# board_sch.net
KiCad netlist of a schematic drawn in Altium Designer
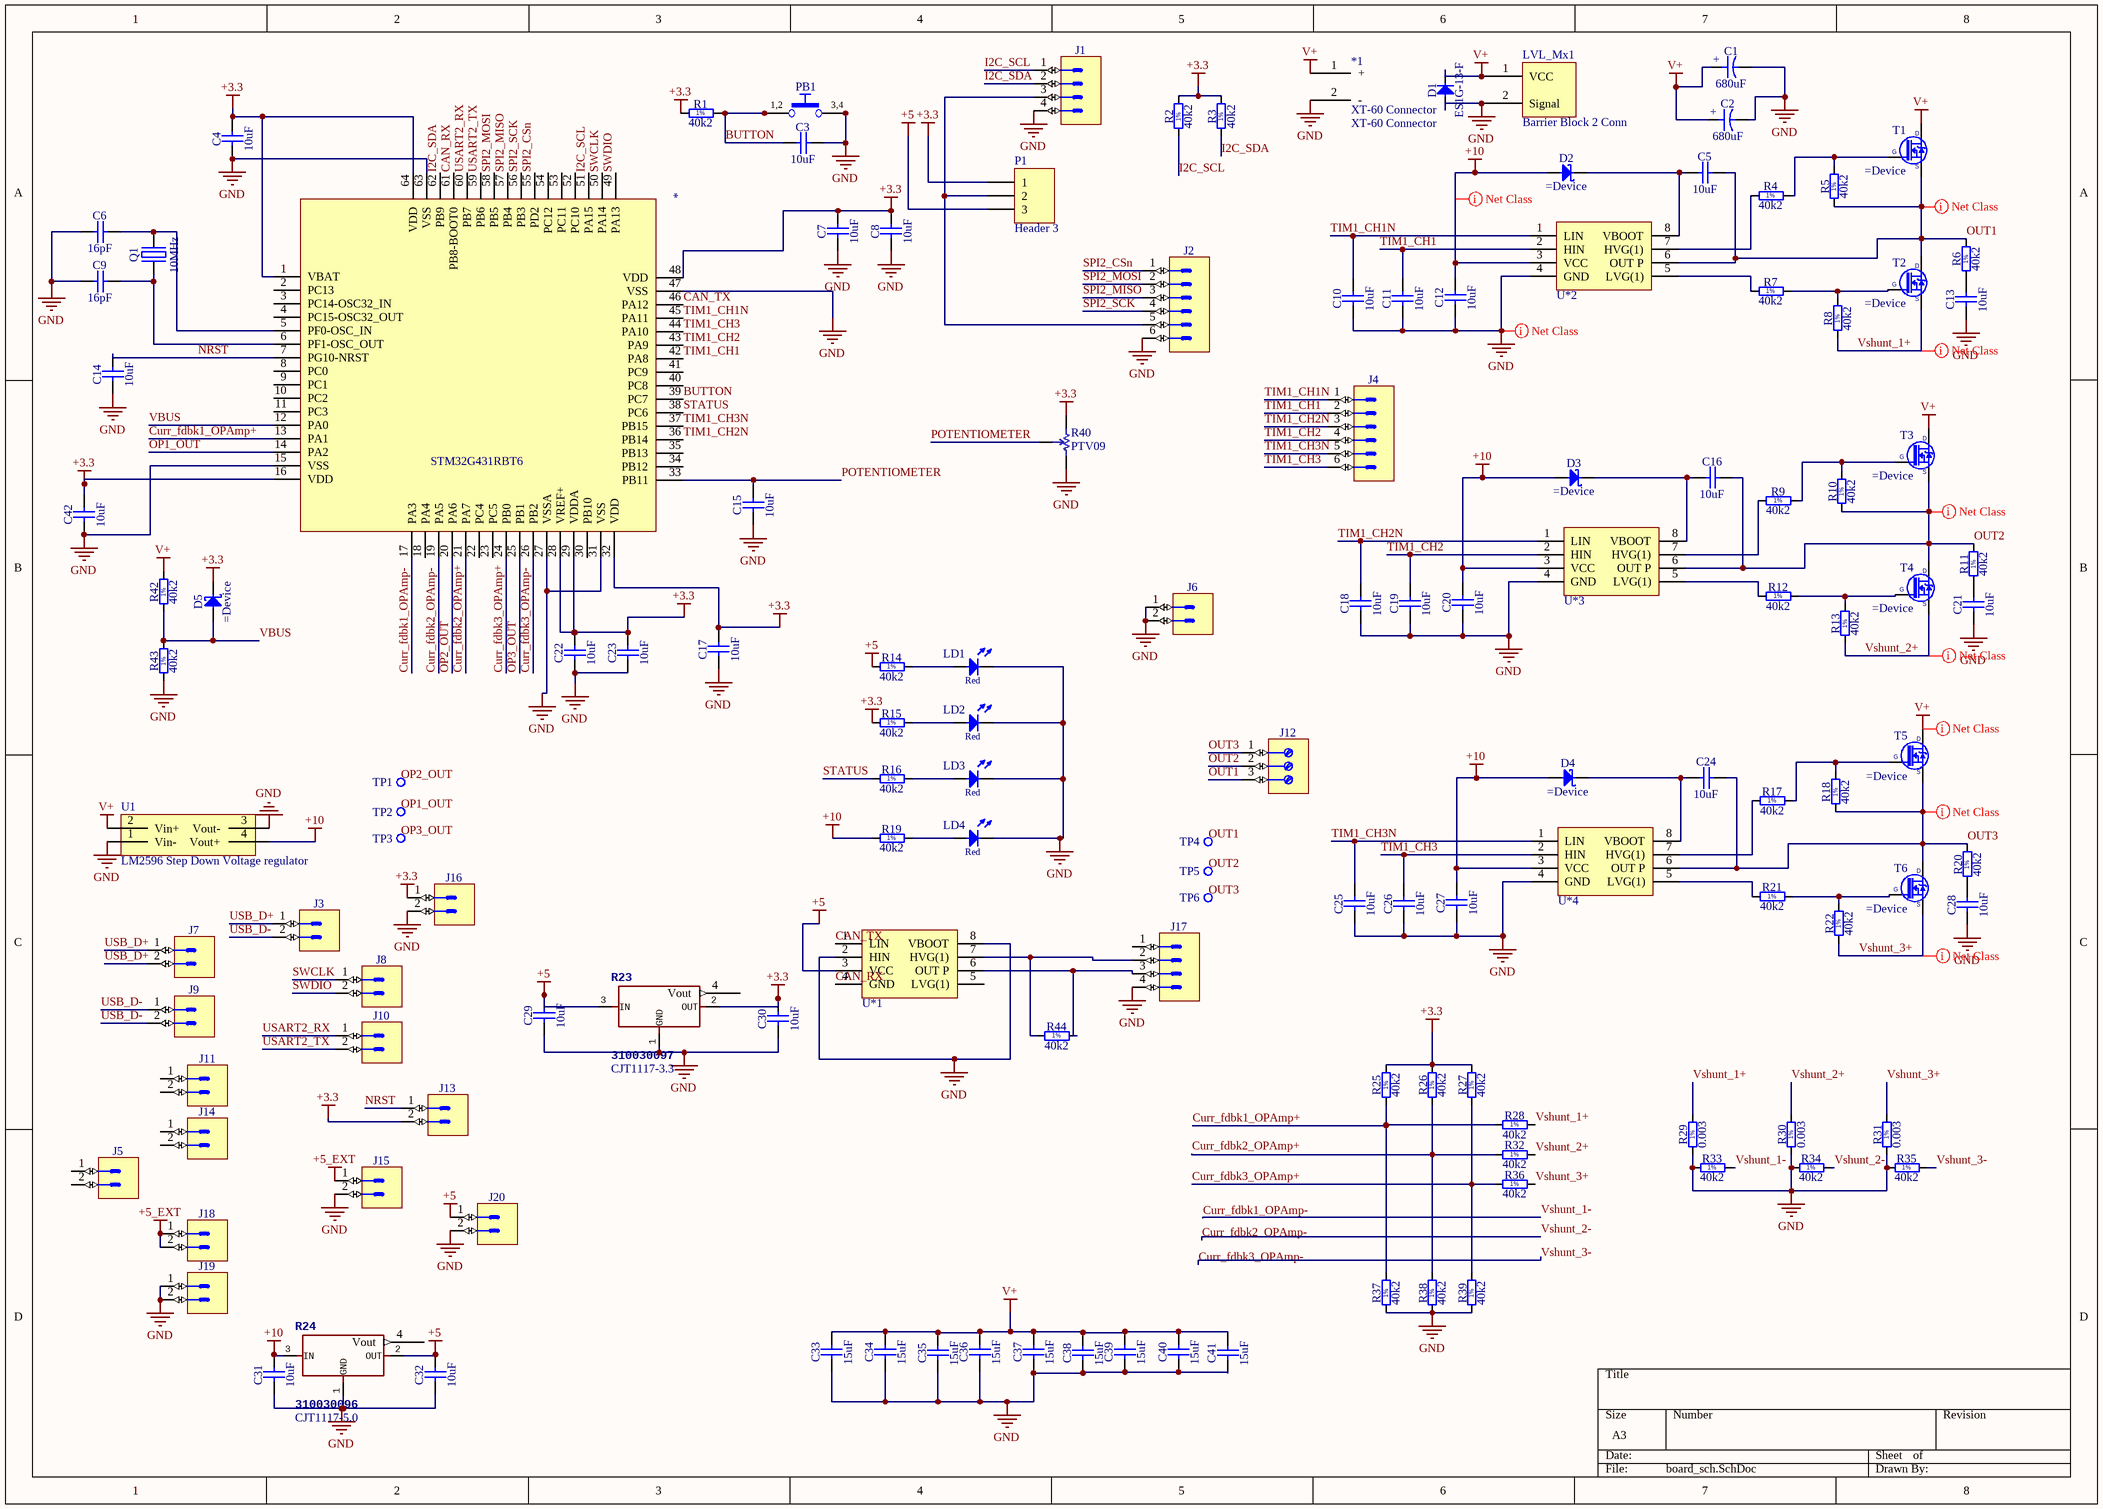
[diagram p0: board_sch.SchDoc]

(export (version "E")
  (design (tool "Eeschema 10.0.6"))
  (components
    (comp (ref "*")
      (value "STM32G431RBT6")
      (footprint "STM-LQFP64_L")
      (libsource (lib "lib") (part "STM32G431RBT6"))
    )
    (comp (ref "*1")
      (value "XT-60 Connector")
      (footprint "XT-60")
      (fields
        (field (name "MANUFACTURER") "POLOLU")
        (field (name "MANUFACTURER PART NUMBER") "XT60 YELLOW")
        (field (name "SUPPLIER PART NUMBER 1") "XT-60 Connector")
      )
      (libsource (lib "AltiumLibraryDDT") (part "XT-60 Connector"))
    )
    (comp (ref "C1")
      (value "680uF")
      (footprint "CAPAE1030X1020N")
      (description "Polarised capacitor")
      (fields
        (field (name "PART NUMBER") "CAE1030-1020_680UF_4V_20%")
        (field (name "VOLTAGE") "4V")
        (field (name "AUTHOR") "CERN DEM MR")
      )
      (libsource (lib "Capacitors") (part "Capacitor - polarized"))
    )
    (comp (ref "C2")
      (value "680uF")
      (footprint "CAPAE1030X1020N")
      (description "Polarised capacitor")
      (fields
        (field (name "PART NUMBER") "CAE1030-1020_680UF_4V_20%")
        (field (name "VOLTAGE") "4V")
        (field (name "AUTHOR") "CERN DEM MR")
      )
      (libsource (lib "Capacitors") (part "Capacitor - polarized"))
    )
    (comp (ref "C3")
      (value "10uF")
      (footprint "CAPC2012X135N")
      (description "Non-polarised capacitor")
      (fields
        (field (name "PART NUMBER") "CC0805_10UF_10V_10%_X7R")
        (field (name "VOLTAGE") "10V")
        (field (name "AUTHOR") "CERN DEM JLC")
      )
      (libsource (lib "Capacitors") (part "Capacitor - non polarized"))
    )
    (comp (ref "C4")
      (value "10uF")
      (footprint "CAPC2012X135N")
      (description "Non-polarised capacitor")
      (fields
        (field (name "PART NUMBER") "CC0805_10UF_10V_10%_X7R")
        (field (name "VOLTAGE") "10V")
        (field (name "AUTHOR") "CERN DEM JLC")
      )
      (libsource (lib "Capacitors") (part "Capacitor - non polarized"))
    )
    (comp (ref "C5")
      (value "10uF")
      (footprint "CAPC2012X135N")
      (description "Non-polarised capacitor")
      (fields
        (field (name "PART NUMBER") "CC0805_10UF_10V_10%_X7R")
        (field (name "VOLTAGE") "10V")
        (field (name "AUTHOR") "CERN DEM JLC")
      )
      (libsource (lib "Capacitors") (part "Capacitor - non polarized"))
    )
    (comp (ref "C6")
      (value "16pF")
      (footprint "CAPC2012X135N")
      (description "Non-polarised capacitor")
      (fields
        (field (name "PART NUMBER") "CC0805_10UF_10V_10%_X7R")
        (field (name "VOLTAGE") "10V")
        (field (name "AUTHOR") "CERN DEM JLC")
      )
      (libsource (lib "Capacitors") (part "Capacitor - non polarized"))
    )
    (comp (ref "C7")
      (value "10uF")
      (footprint "CAPC2012X135N")
      (description "Non-polarised capacitor")
      (fields
        (field (name "PART NUMBER") "CC0805_10UF_10V_10%_X7R")
        (field (name "VOLTAGE") "10V")
        (field (name "AUTHOR") "CERN DEM JLC")
      )
      (libsource (lib "Capacitors") (part "Capacitor - non polarized"))
    )
    (comp (ref "C8")
      (value "10uF")
      (footprint "CAPC2012X135N")
      (description "Non-polarised capacitor")
      (fields
        (field (name "PART NUMBER") "CC0805_10UF_10V_10%_X7R")
        (field (name "VOLTAGE") "10V")
        (field (name "AUTHOR") "CERN DEM JLC")
      )
      (libsource (lib "Capacitors") (part "Capacitor - non polarized"))
    )
    (comp (ref "C9")
      (value "16pF")
      (footprint "CAPC2012X135N")
      (description "Non-polarised capacitor")
      (fields
        (field (name "PART NUMBER") "CC0805_10UF_10V_10%_X7R")
        (field (name "VOLTAGE") "10V")
        (field (name "AUTHOR") "CERN DEM JLC")
      )
      (libsource (lib "Capacitors") (part "Capacitor - non polarized"))
    )
    (comp (ref "C10")
      (value "10uF")
      (footprint "CAPC2012X135N")
      (description "Non-polarised capacitor")
      (fields
        (field (name "PART NUMBER") "CC0805_10UF_10V_10%_X7R")
        (field (name "VOLTAGE") "10V")
        (field (name "AUTHOR") "CERN DEM JLC")
      )
      (libsource (lib "Capacitors") (part "Capacitor - non polarized"))
    )
    (comp (ref "C11")
      (value "10uF")
      (footprint "CAPC2012X135N")
      (description "Non-polarised capacitor")
      (fields
        (field (name "PART NUMBER") "CC0805_10UF_10V_10%_X7R")
        (field (name "VOLTAGE") "10V")
        (field (name "AUTHOR") "CERN DEM JLC")
      )
      (libsource (lib "Capacitors") (part "Capacitor - non polarized"))
    )
    (comp (ref "C12")
      (value "10uF")
      (footprint "CAPC2012X135N")
      (description "Non-polarised capacitor")
      (fields
        (field (name "PART NUMBER") "CC0805_10UF_10V_10%_X7R")
        (field (name "VOLTAGE") "10V")
        (field (name "AUTHOR") "CERN DEM JLC")
      )
      (libsource (lib "Capacitors") (part "Capacitor - non polarized"))
    )
    (comp (ref "C13")
      (value "10uF")
      (footprint "CAPC2012X135N")
      (description "Non-polarised capacitor")
      (fields
        (field (name "PART NUMBER") "CC0805_10UF_10V_10%_X7R")
        (field (name "VOLTAGE") "10V")
        (field (name "AUTHOR") "CERN DEM JLC")
      )
      (libsource (lib "Capacitors") (part "Capacitor - non polarized"))
    )
    (comp (ref "C14")
      (value "10uF")
      (footprint "CAPC2012X135N")
      (description "Non-polarised capacitor")
      (fields
        (field (name "PART NUMBER") "CC0805_10UF_10V_10%_X7R")
        (field (name "VOLTAGE") "10V")
        (field (name "AUTHOR") "CERN DEM JLC")
      )
      (libsource (lib "Capacitors") (part "Capacitor - non polarized"))
    )
    (comp (ref "C15")
      (value "10uF")
      (footprint "CAPC2012X135N")
      (description "Non-polarised capacitor")
      (fields
        (field (name "PART NUMBER") "CC0805_10UF_10V_10%_X7R")
        (field (name "VOLTAGE") "10V")
        (field (name "AUTHOR") "CERN DEM JLC")
      )
      (libsource (lib "Capacitors") (part "Capacitor - non polarized"))
    )
    (comp (ref "C16")
      (value "10uF")
      (footprint "CAPC2012X135N")
      (description "Non-polarised capacitor")
      (fields
        (field (name "PART NUMBER") "CC0805_10UF_10V_10%_X7R")
        (field (name "VOLTAGE") "10V")
        (field (name "AUTHOR") "CERN DEM JLC")
      )
      (libsource (lib "Capacitors") (part "Capacitor - non polarized"))
    )
    (comp (ref "C17")
      (value "10uF")
      (footprint "CAPC2012X135N")
      (description "Non-polarised capacitor")
      (fields
        (field (name "PART NUMBER") "CC0805_10UF_10V_10%_X7R")
        (field (name "VOLTAGE") "10V")
        (field (name "AUTHOR") "CERN DEM JLC")
      )
      (libsource (lib "Capacitors") (part "Capacitor - non polarized"))
    )
    (comp (ref "C18")
      (value "10uF")
      (footprint "CAPC2012X135N")
      (description "Non-polarised capacitor")
      (fields
        (field (name "PART NUMBER") "CC0805_10UF_10V_10%_X7R")
        (field (name "VOLTAGE") "10V")
        (field (name "AUTHOR") "CERN DEM JLC")
      )
      (libsource (lib "Capacitors") (part "Capacitor - non polarized"))
    )
    (comp (ref "C19")
      (value "10uF")
      (footprint "CAPC2012X135N")
      (description "Non-polarised capacitor")
      (fields
        (field (name "PART NUMBER") "CC0805_10UF_10V_10%_X7R")
        (field (name "VOLTAGE") "10V")
        (field (name "AUTHOR") "CERN DEM JLC")
      )
      (libsource (lib "Capacitors") (part "Capacitor - non polarized"))
    )
    (comp (ref "C20")
      (value "10uF")
      (footprint "CAPC2012X135N")
      (description "Non-polarised capacitor")
      (fields
        (field (name "PART NUMBER") "CC0805_10UF_10V_10%_X7R")
        (field (name "VOLTAGE") "10V")
        (field (name "AUTHOR") "CERN DEM JLC")
      )
      (libsource (lib "Capacitors") (part "Capacitor - non polarized"))
    )
    (comp (ref "C21")
      (value "10uF")
      (footprint "CAPC2012X135N")
      (description "Non-polarised capacitor")
      (fields
        (field (name "PART NUMBER") "CC0805_10UF_10V_10%_X7R")
        (field (name "VOLTAGE") "10V")
        (field (name "AUTHOR") "CERN DEM JLC")
      )
      (libsource (lib "Capacitors") (part "Capacitor - non polarized"))
    )
    (comp (ref "C22")
      (value "10uF")
      (footprint "CAPC2012X135N")
      (description "Non-polarised capacitor")
      (fields
        (field (name "PART NUMBER") "CC0805_10UF_10V_10%_X7R")
        (field (name "VOLTAGE") "10V")
        (field (name "AUTHOR") "CERN DEM JLC")
      )
      (libsource (lib "Capacitors") (part "Capacitor - non polarized"))
    )
    (comp (ref "C23")
      (value "10uF")
      (footprint "CAPC2012X135N")
      (description "Non-polarised capacitor")
      (fields
        (field (name "PART NUMBER") "CC0805_10UF_10V_10%_X7R")
        (field (name "VOLTAGE") "10V")
        (field (name "AUTHOR") "CERN DEM JLC")
      )
      (libsource (lib "Capacitors") (part "Capacitor - non polarized"))
    )
    (comp (ref "C24")
      (value "10uF")
      (footprint "CAPC2012X135N")
      (description "Non-polarised capacitor")
      (fields
        (field (name "PART NUMBER") "CC0805_10UF_10V_10%_X7R")
        (field (name "VOLTAGE") "10V")
        (field (name "AUTHOR") "CERN DEM JLC")
      )
      (libsource (lib "Capacitors") (part "Capacitor - non polarized"))
    )
    (comp (ref "C25")
      (value "10uF")
      (footprint "CAPC2012X135N")
      (description "Non-polarised capacitor")
      (fields
        (field (name "PART NUMBER") "CC0805_10UF_10V_10%_X7R")
        (field (name "VOLTAGE") "10V")
        (field (name "AUTHOR") "CERN DEM JLC")
      )
      (libsource (lib "Capacitors") (part "Capacitor - non polarized"))
    )
    (comp (ref "C26")
      (value "10uF")
      (footprint "CAPC2012X135N")
      (description "Non-polarised capacitor")
      (fields
        (field (name "PART NUMBER") "CC0805_10UF_10V_10%_X7R")
        (field (name "VOLTAGE") "10V")
        (field (name "AUTHOR") "CERN DEM JLC")
      )
      (libsource (lib "Capacitors") (part "Capacitor - non polarized"))
    )
    (comp (ref "C27")
      (value "10uF")
      (footprint "CAPC2012X135N")
      (description "Non-polarised capacitor")
      (fields
        (field (name "PART NUMBER") "CC0805_10UF_10V_10%_X7R")
        (field (name "VOLTAGE") "10V")
        (field (name "AUTHOR") "CERN DEM JLC")
      )
      (libsource (lib "Capacitors") (part "Capacitor - non polarized"))
    )
    (comp (ref "C28")
      (value "10uF")
      (footprint "CAPC2012X135N")
      (description "Non-polarised capacitor")
      (fields
        (field (name "PART NUMBER") "CC0805_10UF_10V_10%_X7R")
        (field (name "VOLTAGE") "10V")
        (field (name "AUTHOR") "CERN DEM JLC")
      )
      (libsource (lib "Capacitors") (part "Capacitor - non polarized"))
    )
    (comp (ref "C29")
      (value "10uF")
      (footprint "CAPC2012X135N")
      (description "Non-polarised capacitor")
      (fields
        (field (name "PART NUMBER") "CC0805_10UF_10V_10%_X7R")
        (field (name "VOLTAGE") "10V")
        (field (name "AUTHOR") "CERN DEM JLC")
      )
      (libsource (lib "Capacitors") (part "Capacitor - non polarized"))
    )
    (comp (ref "C30")
      (value "10uF")
      (footprint "CAPC2012X135N")
      (description "Non-polarised capacitor")
      (fields
        (field (name "PART NUMBER") "CC0805_10UF_10V_10%_X7R")
        (field (name "VOLTAGE") "10V")
        (field (name "AUTHOR") "CERN DEM JLC")
      )
      (libsource (lib "Capacitors") (part "Capacitor - non polarized"))
    )
    (comp (ref "C31")
      (value "10uF")
      (footprint "CAPC2012X135N")
      (description "Non-polarised capacitor")
      (fields
        (field (name "PART NUMBER") "CC0805_10UF_10V_10%_X7R")
        (field (name "VOLTAGE") "10V")
        (field (name "AUTHOR") "CERN DEM JLC")
      )
      (libsource (lib "Capacitors") (part "Capacitor - non polarized"))
    )
    (comp (ref "C32")
      (value "10uF")
      (footprint "CAPC2012X135N")
      (description "Non-polarised capacitor")
      (fields
        (field (name "PART NUMBER") "CC0805_10UF_10V_10%_X7R")
        (field (name "VOLTAGE") "10V")
        (field (name "AUTHOR") "CERN DEM JLC")
      )
      (libsource (lib "Capacitors") (part "Capacitor - non polarized"))
    )
    (comp (ref "C33")
      (value "15uF")
      (footprint "CAPC2012X135N")
      (description "Non-polarised capacitor")
      (fields
        (field (name "PART NUMBER") "CC0805_1.2PF_50V_0.25PF_NP0")
        (field (name "VOLTAGE") "50V")
        (field (name "AUTHOR") "CERN DEM JLC")
      )
      (libsource (lib "Capacitors") (part "Capacitor - non polarized"))
    )
    (comp (ref "C34")
      (value "15uF")
      (footprint "CAPC2012X135N")
      (description "Non-polarised capacitor")
      (fields
        (field (name "PART NUMBER") "CC0805_1.2PF_50V_0.25PF_NP0")
        (field (name "VOLTAGE") "50V")
        (field (name "AUTHOR") "CERN DEM JLC")
      )
      (libsource (lib "Capacitors") (part "Capacitor - non polarized"))
    )
    (comp (ref "C35")
      (value "15uF")
      (footprint "CAPC2012X135N")
      (description "Non-polarised capacitor")
      (fields
        (field (name "PART NUMBER") "CC0805_1.2PF_50V_0.25PF_NP0")
        (field (name "VOLTAGE") "50V")
        (field (name "AUTHOR") "CERN DEM JLC")
      )
      (libsource (lib "Capacitors") (part "Capacitor - non polarized"))
    )
    (comp (ref "C36")
      (value "15uF")
      (footprint "CAPC2012X135N")
      (description "Non-polarised capacitor")
      (fields
        (field (name "PART NUMBER") "CC0805_1.2PF_50V_0.25PF_NP0")
        (field (name "VOLTAGE") "50V")
        (field (name "AUTHOR") "CERN DEM JLC")
      )
      (libsource (lib "Capacitors") (part "Capacitor - non polarized"))
    )
    (comp (ref "C37")
      (value "15uF")
      (footprint "CAPC2012X135N")
      (description "Non-polarised capacitor")
      (fields
        (field (name "PART NUMBER") "CC0805_1.2PF_50V_0.25PF_NP0")
        (field (name "VOLTAGE") "50V")
        (field (name "AUTHOR") "CERN DEM JLC")
      )
      (libsource (lib "Capacitors") (part "Capacitor - non polarized"))
    )
    (comp (ref "C38")
      (value "15uF")
      (footprint "CAPC2012X135N")
      (description "Non-polarised capacitor")
      (fields
        (field (name "PART NUMBER") "CC0805_1.2PF_50V_0.25PF_NP0")
        (field (name "VOLTAGE") "50V")
        (field (name "AUTHOR") "CERN DEM JLC")
      )
      (libsource (lib "Capacitors") (part "Capacitor - non polarized"))
    )
    (comp (ref "C39")
      (value "15uF")
      (footprint "CAPC2012X135N")
      (description "Non-polarised capacitor")
      (fields
        (field (name "PART NUMBER") "CC0805_1.2PF_50V_0.25PF_NP0")
        (field (name "VOLTAGE") "50V")
        (field (name "AUTHOR") "CERN DEM JLC")
      )
      (libsource (lib "Capacitors") (part "Capacitor - non polarized"))
    )
    (comp (ref "C40")
      (value "15uF")
      (footprint "CAPC2012X135N")
      (description "Non-polarised capacitor")
      (fields
        (field (name "PART NUMBER") "CC0805_1.2PF_50V_0.25PF_NP0")
        (field (name "VOLTAGE") "50V")
        (field (name "AUTHOR") "CERN DEM JLC")
      )
      (libsource (lib "Capacitors") (part "Capacitor - non polarized"))
    )
    (comp (ref "C41")
      (value "15uF")
      (footprint "CAPC2012X135N")
      (description "Non-polarised capacitor")
      (fields
        (field (name "PART NUMBER") "CC0805_1.2PF_50V_0.25PF_NP0")
        (field (name "VOLTAGE") "50V")
        (field (name "AUTHOR") "CERN DEM JLC")
      )
      (libsource (lib "Capacitors") (part "Capacitor - non polarized"))
    )
    (comp (ref "C42")
      (value "10uF")
      (footprint "CAPC2012X135N")
      (description "Non-polarised capacitor")
      (fields
        (field (name "PART NUMBER") "CC0805_10UF_10V_10%_X7R")
        (field (name "VOLTAGE") "10V")
        (field (name "AUTHOR") "CERN DEM JLC")
      )
      (libsource (lib "Capacitors") (part "Capacitor - non polarized"))
    )
    (comp (ref "D1")
      (value "ES1G-13-F")
      (footprint "DIOM5226X230N")
      (description "Diode")
      (fields
        (field (name "VOLTAGE") "400V")
        (field (name "POWER") "1A")
        (field (name "AUTHOR") "CERN DEM JLC")
      )
      (libsource (lib "ICs And Semiconductors") (part "Diode"))
    )
    (comp (ref "D2")
      (value "~")
      (footprint "SOD3716X135N")
      (description "Schottky Diode")
      (libsource (lib "Diodes") (part "Diode Schottky"))
    )
    (comp (ref "D3")
      (value "~")
      (footprint "SOD3716X135N")
      (description "Schottky Diode")
      (libsource (lib "Diodes") (part "Diode Schottky"))
    )
    (comp (ref "D4")
      (value "~")
      (footprint "SOD3716X135N")
      (description "Schottky Diode")
      (libsource (lib "Diodes") (part "Diode Schottky"))
    )
    (comp (ref "D5")
      (value "~")
      (footprint "SOD3716X135N")
      (description "Schottky Diode")
      (libsource (lib "Diodes") (part "Diode Schottky"))
    )
    (comp (ref "J1")
      (value "KK®")
      (footprint "MOLEX_22-04-1041")
      (description "Connector 4 Male")
      (fields
        (field (name "PART NUMBER") "MOLEX_22-04-1041")
        (field (name "MANUFACTURER") "MOLEX")
        (field (name "AUTHOR") "CERN DEM JLC")
      )
      (libsource (lib "Connectors") (part "Connector 4 Male"))
    )
    (comp (ref "J2")
      (value "KK®")
      (footprint "MOLEX_22-27-2061")
      (description "Connector 6 Male")
      (fields
        (field (name "PART NUMBER") "MOLEX_22-27-2061")
        (field (name "MANUFACTURER") "MOLEX")
        (field (name "AUTHOR") "CERN DEM JMW")
      )
      (libsource (lib "Connectors") (part "Connector 6 Male"))
    )
    (comp (ref "J3")
      (value "Header 2")
      (footprint "SAMTEC_TSW-101-23-L-D")
      (description "Connector 2 Male")
      (fields
        (field (name "PART NUMBER") "SAMTEC_TSW-101-23-L-D")
        (field (name "MANUFACTURER") "SAMTEC")
        (field (name "AUTHOR") "CERN DEM MR")
      )
      (libsource (lib "Connectors") (part "Connector 2 Male"))
    )
    (comp (ref "J4")
      (value "~")
      (footprint "HARWIN_M22-F2010605")
      (description "Connector 6 Male")
      (fields
        (field (name "PART NUMBER") "HARWIN_M22-F2010605")
        (field (name "MANUFACTURER") "HARWIN")
        (field (name "AUTHOR") "CERN DEM JLC")
      )
      (libsource (lib "Connectors") (part "Connector 6 Male"))
    )
    (comp (ref "J5")
      (value "Header 2")
      (footprint "SAMTEC_TSW-101-23-L-D")
      (description "Connector 2 Male")
      (fields
        (field (name "PART NUMBER") "SAMTEC_TSW-101-23-L-D")
        (field (name "MANUFACTURER") "SAMTEC")
        (field (name "AUTHOR") "CERN DEM MR")
      )
      (libsource (lib "Connectors") (part "Connector 2 Male"))
    )
    (comp (ref "J6")
      (value "Header 2")
      (footprint "HARWIN_M22-2010205")
      (description "Connector 2 Male")
      (fields
        (field (name "PART NUMBER") "HARWIN_M22-2010205")
        (field (name "MANUFACTURER") "HARWIN")
        (field (name "AUTHOR") "CERN DEM JLC")
      )
      (libsource (lib "Connectors") (part "Connector 2 Male"))
    )
    (comp (ref "J7")
      (value "Header 2")
      (footprint "SAMTEC_TSW-101-23-L-D")
      (description "Connector 2 Male")
      (fields
        (field (name "PART NUMBER") "SAMTEC_TSW-101-23-L-D")
        (field (name "MANUFACTURER") "SAMTEC")
        (field (name "AUTHOR") "CERN DEM MR")
      )
      (libsource (lib "Connectors") (part "Connector 2 Male"))
    )
    (comp (ref "J8")
      (value "Header 2")
      (footprint "SAMTEC_TSW-101-23-L-D")
      (description "Connector 2 Male")
      (fields
        (field (name "PART NUMBER") "SAMTEC_TSW-101-23-L-D")
        (field (name "MANUFACTURER") "SAMTEC")
        (field (name "AUTHOR") "CERN DEM MR")
      )
      (libsource (lib "Connectors") (part "Connector 2 Male"))
    )
    (comp (ref "J9")
      (value "Header 2")
      (footprint "SAMTEC_TSW-101-23-L-D")
      (description "Connector 2 Male")
      (fields
        (field (name "PART NUMBER") "SAMTEC_TSW-101-23-L-D")
        (field (name "MANUFACTURER") "SAMTEC")
        (field (name "AUTHOR") "CERN DEM MR")
      )
      (libsource (lib "Connectors") (part "Connector 2 Male"))
    )
    (comp (ref "J10")
      (value "Header 2")
      (footprint "SAMTEC_TSW-101-23-L-D")
      (description "Connector 2 Male")
      (fields
        (field (name "PART NUMBER") "SAMTEC_TSW-101-23-L-D")
        (field (name "MANUFACTURER") "SAMTEC")
        (field (name "AUTHOR") "CERN DEM MR")
      )
      (libsource (lib "Connectors") (part "Connector 2 Male"))
    )
    (comp (ref "J11")
      (value "Header 2")
      (footprint "SAMTEC_TSW-101-23-L-D")
      (description "Connector 2 Male")
      (fields
        (field (name "PART NUMBER") "SAMTEC_TSW-101-23-L-D")
        (field (name "MANUFACTURER") "SAMTEC")
        (field (name "AUTHOR") "CERN DEM MR")
      )
      (libsource (lib "Connectors") (part "Connector 2 Male"))
    )
    (comp (ref "J12")
      (value "Terminal")
      (footprint "WIELAND_25.161.0353.0")
      (description "Terminal Block, 3 Positions, Screw Connection")
      (fields
        (field (name "PART NUMBER") "WIELAND_25.161.0353.0")
        (field (name "MANUFACTURER") "WIELAND")
        (field (name "AUTHOR") "CERN DEM JLC")
      )
      (libsource (lib "Connectors") (part "Terminal Block_3 Positions_Screw Connection"))
    )
    (comp (ref "J13")
      (value "Header 2")
      (footprint "SAMTEC_TSW-101-23-L-D")
      (description "Connector 2 Male")
      (fields
        (field (name "PART NUMBER") "SAMTEC_TSW-101-23-L-D")
        (field (name "MANUFACTURER") "SAMTEC")
        (field (name "AUTHOR") "CERN DEM MR")
      )
      (libsource (lib "Connectors") (part "Connector 2 Male"))
    )
    (comp (ref "J14")
      (value "Header 2")
      (footprint "SAMTEC_TSW-101-23-L-D")
      (description "Connector 2 Male")
      (fields
        (field (name "PART NUMBER") "SAMTEC_TSW-101-23-L-D")
        (field (name "MANUFACTURER") "SAMTEC")
        (field (name "AUTHOR") "CERN DEM MR")
      )
      (libsource (lib "Connectors") (part "Connector 2 Male"))
    )
    (comp (ref "J15")
      (value "Header 2")
      (footprint "SAMTEC_TSW-101-23-L-D")
      (description "Connector 2 Male")
      (fields
        (field (name "PART NUMBER") "SAMTEC_TSW-101-23-L-D")
        (field (name "MANUFACTURER") "SAMTEC")
        (field (name "AUTHOR") "CERN DEM MR")
      )
      (libsource (lib "Connectors") (part "Connector 2 Male"))
    )
    (comp (ref "J16")
      (value "Header 2")
      (footprint "SAMTEC_TSW-101-23-L-D")
      (description "Connector 2 Male")
      (fields
        (field (name "PART NUMBER") "SAMTEC_TSW-101-23-L-D")
        (field (name "MANUFACTURER") "SAMTEC")
        (field (name "AUTHOR") "CERN DEM MR")
      )
      (libsource (lib "Connectors") (part "Connector 2 Male"))
    )
    (comp (ref "J17")
      (value "KK®")
      (footprint "MOLEX_22-04-1041")
      (description "Connector 4 Male")
      (fields
        (field (name "PART NUMBER") "MOLEX_22-04-1041")
        (field (name "MANUFACTURER") "MOLEX")
        (field (name "AUTHOR") "CERN DEM JLC")
      )
      (libsource (lib "Connectors") (part "Connector 4 Male"))
    )
    (comp (ref "J18")
      (value "Header 2")
      (footprint "SAMTEC_TSW-101-23-L-D")
      (description "Connector 2 Male")
      (fields
        (field (name "PART NUMBER") "SAMTEC_TSW-101-23-L-D")
        (field (name "MANUFACTURER") "SAMTEC")
        (field (name "AUTHOR") "CERN DEM MR")
      )
      (libsource (lib "Connectors") (part "Connector 2 Male"))
    )
    (comp (ref "J19")
      (value "Header 2")
      (footprint "SAMTEC_TSW-101-23-L-D")
      (description "Connector 2 Male")
      (fields
        (field (name "PART NUMBER") "SAMTEC_TSW-101-23-L-D")
        (field (name "MANUFACTURER") "SAMTEC")
        (field (name "AUTHOR") "CERN DEM MR")
      )
      (libsource (lib "Connectors") (part "Connector 2 Male"))
    )
    (comp (ref "J20")
      (value "Header 2")
      (footprint "SAMTEC_TSW-101-23-L-D")
      (description "Connector 2 Male")
      (fields
        (field (name "PART NUMBER") "SAMTEC_TSW-101-23-L-D")
        (field (name "MANUFACTURER") "SAMTEC")
        (field (name "AUTHOR") "CERN DEM MR")
      )
      (libsource (lib "Connectors") (part "Connector 2 Male"))
    )
    (comp (ref "LD1")
      (value "Red")
      (footprint "LED_5MM_RED_1C-2A")
      (description "LED Red 1C 2A")
      (fields
        (field (name "PART NUMBER") "LED_AVAGO_HLMP-3301")
        (field (name "MANUFACTURER") "AVAGO TECHNOLOGIES")
        (field (name "AUTHOR") "CERN DEM JLC")
      )
      (libsource (lib "ICs And Semiconductors") (part "LED Red 1C 2A"))
    )
    (comp (ref "LD2")
      (value "Red")
      (footprint "LED_5MM_RED_1C-2A")
      (description "LED Red 1C 2A")
      (fields
        (field (name "PART NUMBER") "LED_AVAGO_HLMP-3301")
        (field (name "MANUFACTURER") "AVAGO TECHNOLOGIES")
        (field (name "AUTHOR") "CERN DEM JLC")
      )
      (libsource (lib "ICs And Semiconductors") (part "LED Red 1C 2A"))
    )
    (comp (ref "LD3")
      (value "Red")
      (footprint "LED_5MM_RED_1C-2A")
      (description "LED Red 1C 2A")
      (fields
        (field (name "PART NUMBER") "LED_AVAGO_HLMP-3301")
        (field (name "MANUFACTURER") "AVAGO TECHNOLOGIES")
        (field (name "AUTHOR") "CERN DEM JLC")
      )
      (libsource (lib "ICs And Semiconductors") (part "LED Red 1C 2A"))
    )
    (comp (ref "LD4")
      (value "Red")
      (footprint "LED_5MM_RED_1C-2A")
      (description "LED Red 1C 2A")
      (fields
        (field (name "PART NUMBER") "LED_AVAGO_HLMP-3301")
        (field (name "MANUFACTURER") "AVAGO TECHNOLOGIES")
        (field (name "AUTHOR") "CERN DEM JLC")
      )
      (libsource (lib "ICs And Semiconductors") (part "LED Red 1C 2A"))
    )
    (comp (ref "LVL_Mx1")
      (value "Barrier Block 2 Conn")
      (footprint "2 Barrier Block 5mm")
      (libsource (lib "AltiumLibraryDDT") (part "Barrier Block 2 Conn_1"))
    )
    (comp (ref "P1")
      (value "Header 3")
      (footprint "HDR1X3")
      (description "Header, 3-Pin")
      (fields (field (name "PUBLISHER") "Altium Limited"))
      (libsource (lib "Miscellaneous Connectors") (part "Header 3"))
    )
    (comp (ref "PB1")
      (value "Push Button")
      (footprint "PB_TYCO_FSM2JSMA")
      (description "Push-Button Switch SPDT")
      (fields
        (field (name "PART NUMBER") "PB_TYCO_FSM2JSMA")
        (field (name "MANUFACTURER") "TYCO ELECTRONICS")
        (field (name "AUTHOR") "CERN DEM JLC")
      )
      (libsource (lib "Eletro-mechanical") (part "PB SPST 12NO-34NO"))
    )
    (comp (ref "Q1")
      (value "10MHz")
      (footprint "XTAL1160X490X430")
      (description "Quartz Crystal")
      (fields
        (field (name "PART NUMBER") "XTAL_10MHZ_IQD_LFXTAL003166")
        (field (name "MANUFACTURER") "IQD FREQUENCY PRODUCTS")
        (field (name "AUTHOR") "CERN DEM JLC")
      )
      (libsource (lib "ICs And Semiconductors") (part "Quartz Crystal"))
    )
    (comp (ref "R1")
      (value "40k2")
      (footprint "RESC2012X60N")
      (description "Resistor - 1%")
      (fields
        (field (name "PART NUMBER") "R0805_40K2_1%_0.125W_100PPM")
        (field (name "POWER") "0.125W")
        (field (name "AUTHOR") "CERN DEM JLC")
      )
      (libsource (lib "Resistors") (part "Resistor - 1%"))
    )
    (comp (ref "R2")
      (value "40k2")
      (footprint "RESC2012X60N")
      (description "Resistor - 1%")
      (fields
        (field (name "PART NUMBER") "R0805_40K2_1%_0.125W_100PPM")
        (field (name "POWER") "0.125W")
        (field (name "AUTHOR") "CERN DEM JLC")
      )
      (libsource (lib "Resistors") (part "Resistor - 1%"))
    )
    (comp (ref "R3")
      (value "40k2")
      (footprint "RESC2012X60N")
      (description "Resistor - 1%")
      (fields
        (field (name "PART NUMBER") "R0805_40K2_1%_0.125W_100PPM")
        (field (name "POWER") "0.125W")
        (field (name "AUTHOR") "CERN DEM JLC")
      )
      (libsource (lib "Resistors") (part "Resistor - 1%"))
    )
    (comp (ref "R4")
      (value "40k2")
      (footprint "RESC2012X60N")
      (description "Resistor - 1%")
      (fields
        (field (name "PART NUMBER") "R0805_40K2_1%_0.125W_100PPM")
        (field (name "POWER") "0.125W")
        (field (name "AUTHOR") "CERN DEM JLC")
      )
      (libsource (lib "Resistors") (part "Resistor - 1%"))
    )
    (comp (ref "R5")
      (value "40k2")
      (footprint "RESC2012X60N")
      (description "Resistor - 1%")
      (fields
        (field (name "PART NUMBER") "R0805_40K2_1%_0.125W_100PPM")
        (field (name "POWER") "0.125W")
        (field (name "AUTHOR") "CERN DEM JLC")
      )
      (libsource (lib "Resistors") (part "Resistor - 1%"))
    )
    (comp (ref "R6")
      (value "40k2")
      (footprint "RESC2012X60N")
      (description "Resistor - 1%")
      (fields
        (field (name "PART NUMBER") "R0805_40K2_1%_0.125W_100PPM")
        (field (name "POWER") "0.125W")
        (field (name "AUTHOR") "CERN DEM JLC")
      )
      (libsource (lib "Resistors") (part "Resistor - 1%"))
    )
    (comp (ref "R7")
      (value "40k2")
      (footprint "RESC2012X60N")
      (description "Resistor - 1%")
      (fields
        (field (name "PART NUMBER") "R0805_40K2_1%_0.125W_100PPM")
        (field (name "POWER") "0.125W")
        (field (name "AUTHOR") "CERN DEM JLC")
      )
      (libsource (lib "Resistors") (part "Resistor - 1%"))
    )
    (comp (ref "R8")
      (value "40k2")
      (footprint "RESC2012X60N")
      (description "Resistor - 1%")
      (fields
        (field (name "PART NUMBER") "R0805_40K2_1%_0.125W_100PPM")
        (field (name "POWER") "0.125W")
        (field (name "AUTHOR") "CERN DEM JLC")
      )
      (libsource (lib "Resistors") (part "Resistor - 1%"))
    )
    (comp (ref "R9")
      (value "40k2")
      (footprint "RESC2012X60N")
      (description "Resistor - 1%")
      (fields
        (field (name "PART NUMBER") "R0805_40K2_1%_0.125W_100PPM")
        (field (name "POWER") "0.125W")
        (field (name "AUTHOR") "CERN DEM JLC")
      )
      (libsource (lib "Resistors") (part "Resistor - 1%"))
    )
    (comp (ref "R10")
      (value "40k2")
      (footprint "RESC2012X60N")
      (description "Resistor - 1%")
      (fields
        (field (name "PART NUMBER") "R0805_40K2_1%_0.125W_100PPM")
        (field (name "POWER") "0.125W")
        (field (name "AUTHOR") "CERN DEM JLC")
      )
      (libsource (lib "Resistors") (part "Resistor - 1%"))
    )
    (comp (ref "R11")
      (value "40k2")
      (footprint "RESC2012X60N")
      (description "Resistor - 1%")
      (fields
        (field (name "PART NUMBER") "R0805_40K2_1%_0.125W_100PPM")
        (field (name "POWER") "0.125W")
        (field (name "AUTHOR") "CERN DEM JLC")
      )
      (libsource (lib "Resistors") (part "Resistor - 1%"))
    )
    (comp (ref "R12")
      (value "40k2")
      (footprint "RESC2012X60N")
      (description "Resistor - 1%")
      (fields
        (field (name "PART NUMBER") "R0805_40K2_1%_0.125W_100PPM")
        (field (name "POWER") "0.125W")
        (field (name "AUTHOR") "CERN DEM JLC")
      )
      (libsource (lib "Resistors") (part "Resistor - 1%"))
    )
    (comp (ref "R13")
      (value "40k2")
      (footprint "RESC2012X60N")
      (description "Resistor - 1%")
      (fields
        (field (name "PART NUMBER") "R0805_40K2_1%_0.125W_100PPM")
        (field (name "POWER") "0.125W")
        (field (name "AUTHOR") "CERN DEM JLC")
      )
      (libsource (lib "Resistors") (part "Resistor - 1%"))
    )
    (comp (ref "R14")
      (value "40k2")
      (footprint "RESC2012X60N")
      (description "Resistor - 1%")
      (fields
        (field (name "PART NUMBER") "R0805_40K2_1%_0.125W_100PPM")
        (field (name "POWER") "0.125W")
        (field (name "AUTHOR") "CERN DEM JLC")
      )
      (libsource (lib "Resistors") (part "Resistor - 1%"))
    )
    (comp (ref "R15")
      (value "40k2")
      (footprint "RESC2012X60N")
      (description "Resistor - 1%")
      (fields
        (field (name "PART NUMBER") "R0805_40K2_1%_0.125W_100PPM")
        (field (name "POWER") "0.125W")
        (field (name "AUTHOR") "CERN DEM JLC")
      )
      (libsource (lib "Resistors") (part "Resistor - 1%"))
    )
    (comp (ref "R16")
      (value "40k2")
      (footprint "RESC2012X60N")
      (description "Resistor - 1%")
      (fields
        (field (name "PART NUMBER") "R0805_40K2_1%_0.125W_100PPM")
        (field (name "POWER") "0.125W")
        (field (name "AUTHOR") "CERN DEM JLC")
      )
      (libsource (lib "Resistors") (part "Resistor - 1%"))
    )
    (comp (ref "R17")
      (value "40k2")
      (footprint "RESC2012X60N")
      (description "Resistor - 1%")
      (fields
        (field (name "PART NUMBER") "R0805_40K2_1%_0.125W_100PPM")
        (field (name "POWER") "0.125W")
        (field (name "AUTHOR") "CERN DEM JLC")
      )
      (libsource (lib "Resistors") (part "Resistor - 1%"))
    )
    (comp (ref "R18")
      (value "40k2")
      (footprint "RESC2012X60N")
      (description "Resistor - 1%")
      (fields
        (field (name "PART NUMBER") "R0805_40K2_1%_0.125W_100PPM")
        (field (name "POWER") "0.125W")
        (field (name "AUTHOR") "CERN DEM JLC")
      )
      (libsource (lib "Resistors") (part "Resistor - 1%"))
    )
    (comp (ref "R19")
      (value "40k2")
      (footprint "RESC2012X60N")
      (description "Resistor - 1%")
      (fields
        (field (name "PART NUMBER") "R0805_40K2_1%_0.125W_100PPM")
        (field (name "POWER") "0.125W")
        (field (name "AUTHOR") "CERN DEM JLC")
      )
      (libsource (lib "Resistors") (part "Resistor - 1%"))
    )
    (comp (ref "R20")
      (value "40k2")
      (footprint "RESC2012X60N")
      (description "Resistor - 1%")
      (fields
        (field (name "PART NUMBER") "R0805_40K2_1%_0.125W_100PPM")
        (field (name "POWER") "0.125W")
        (field (name "AUTHOR") "CERN DEM JLC")
      )
      (libsource (lib "Resistors") (part "Resistor - 1%"))
    )
    (comp (ref "R21")
      (value "40k2")
      (footprint "RESC2012X60N")
      (description "Resistor - 1%")
      (fields
        (field (name "PART NUMBER") "R0805_40K2_1%_0.125W_100PPM")
        (field (name "POWER") "0.125W")
        (field (name "AUTHOR") "CERN DEM JLC")
      )
      (libsource (lib "Resistors") (part "Resistor - 1%"))
    )
    (comp (ref "R22")
      (value "40k2")
      (footprint "RESC2012X60N")
      (description "Resistor - 1%")
      (fields
        (field (name "PART NUMBER") "R0805_40K2_1%_0.125W_100PPM")
        (field (name "POWER") "0.125W")
        (field (name "AUTHOR") "CERN DEM JLC")
      )
      (libsource (lib "Resistors") (part "Resistor - 1%"))
    )
    (comp (ref "R23")
      (value "310030097")
      (footprint "SOT-223")
      (fields (field (name "MPN") "CJT1117-3.3"))
      (libsource (lib "AltiumLibraryDDT") (part "PMIC-CJT1117-3.3(SOT223)"))
    )
    (comp (ref "R24")
      (value "310030096")
      (footprint "SOT-223")
      (fields (field (name "MPN") "CJT1117-5.0"))
      (libsource (lib "AltiumLibraryDDT") (part "PMIC-CJT1117-5.0(SOT223)"))
    )
    (comp (ref "R25")
      (value "40k2")
      (footprint "RESC2012X60N")
      (description "Resistor - 1%")
      (fields
        (field (name "PART NUMBER") "R0805_40K2_1%_0.125W_100PPM")
        (field (name "POWER") "0.125W")
        (field (name "AUTHOR") "CERN DEM JLC")
      )
      (libsource (lib "Resistors") (part "Resistor - 1%"))
    )
    (comp (ref "R26")
      (value "40k2")
      (footprint "RESC2012X60N")
      (description "Resistor - 1%")
      (fields
        (field (name "PART NUMBER") "R0805_40K2_1%_0.125W_100PPM")
        (field (name "POWER") "0.125W")
        (field (name "AUTHOR") "CERN DEM JLC")
      )
      (libsource (lib "Resistors") (part "Resistor - 1%"))
    )
    (comp (ref "R27")
      (value "40k2")
      (footprint "RESC2012X60N")
      (description "Resistor - 1%")
      (fields
        (field (name "PART NUMBER") "R0805_40K2_1%_0.125W_100PPM")
        (field (name "POWER") "0.125W")
        (field (name "AUTHOR") "CERN DEM JLC")
      )
      (libsource (lib "Resistors") (part "Resistor - 1%"))
    )
    (comp (ref "R28")
      (value "40k2")
      (footprint "RESC2012X60N")
      (description "Resistor - 1%")
      (fields
        (field (name "PART NUMBER") "R0805_40K2_1%_0.125W_100PPM")
        (field (name "POWER") "0.125W")
        (field (name "AUTHOR") "CERN DEM JLC")
      )
      (libsource (lib "Resistors") (part "Resistor - 1%"))
    )
    (comp (ref "R29")
      (value "0.003")
      (footprint "RESC6432X120N")
      (description "Resistor - 1%")
      (fields
        (field (name "PART NUMBER") "R2512_390K_1%_3W_100PPM_TYCO_3522")
        (field (name "POWER") "3W")
        (field (name "AUTHOR") "CERN DEM JLC")
      )
      (libsource (lib "Resistors") (part "Resistor - 1%"))
    )
    (comp (ref "R30")
      (value "0.003")
      (footprint "RESC6432X120N")
      (description "Resistor - 1%")
      (fields
        (field (name "PART NUMBER") "R2512_390K_1%_3W_100PPM_TYCO_3522")
        (field (name "POWER") "3W")
        (field (name "AUTHOR") "CERN DEM JLC")
      )
      (libsource (lib "Resistors") (part "Resistor - 1%"))
    )
    (comp (ref "R31")
      (value "0.003")
      (footprint "RESC6432X120N")
      (description "Resistor - 1%")
      (fields
        (field (name "PART NUMBER") "R2512_390K_1%_3W_100PPM_TYCO_3522")
        (field (name "POWER") "3W")
        (field (name "AUTHOR") "CERN DEM JLC")
      )
      (libsource (lib "Resistors") (part "Resistor - 1%"))
    )
    (comp (ref "R32")
      (value "40k2")
      (footprint "RESC2012X60N")
      (description "Resistor - 1%")
      (fields
        (field (name "PART NUMBER") "R0805_40K2_1%_0.125W_100PPM")
        (field (name "POWER") "0.125W")
        (field (name "AUTHOR") "CERN DEM JLC")
      )
      (libsource (lib "Resistors") (part "Resistor - 1%"))
    )
    (comp (ref "R33")
      (value "40k2")
      (footprint "RESC2012X60N")
      (description "Resistor - 1%")
      (fields
        (field (name "PART NUMBER") "R0805_40K2_1%_0.125W_100PPM")
        (field (name "POWER") "0.125W")
        (field (name "AUTHOR") "CERN DEM JLC")
      )
      (libsource (lib "Resistors") (part "Resistor - 1%"))
    )
    (comp (ref "R34")
      (value "40k2")
      (footprint "RESC2012X60N")
      (description "Resistor - 1%")
      (fields
        (field (name "PART NUMBER") "R0805_40K2_1%_0.125W_100PPM")
        (field (name "POWER") "0.125W")
        (field (name "AUTHOR") "CERN DEM JLC")
      )
      (libsource (lib "Resistors") (part "Resistor - 1%"))
    )
    (comp (ref "R35")
      (value "40k2")
      (footprint "RESC2012X60N")
      (description "Resistor - 1%")
      (fields
        (field (name "PART NUMBER") "R0805_40K2_1%_0.125W_100PPM")
        (field (name "POWER") "0.125W")
        (field (name "AUTHOR") "CERN DEM JLC")
      )
      (libsource (lib "Resistors") (part "Resistor - 1%"))
    )
    (comp (ref "R36")
      (value "40k2")
      (footprint "RESC2012X60N")
      (description "Resistor - 1%")
      (fields
        (field (name "PART NUMBER") "R0805_40K2_1%_0.125W_100PPM")
        (field (name "POWER") "0.125W")
        (field (name "AUTHOR") "CERN DEM JLC")
      )
      (libsource (lib "Resistors") (part "Resistor - 1%"))
    )
    (comp (ref "R37")
      (value "40k2")
      (footprint "RESC2012X60N")
      (description "Resistor - 1%")
      (fields
        (field (name "PART NUMBER") "R0805_40K2_1%_0.125W_100PPM")
        (field (name "POWER") "0.125W")
        (field (name "AUTHOR") "CERN DEM JLC")
      )
      (libsource (lib "Resistors") (part "Resistor - 1%"))
    )
    (comp (ref "R38")
      (value "40k2")
      (footprint "RESC2012X60N")
      (description "Resistor - 1%")
      (fields
        (field (name "PART NUMBER") "R0805_40K2_1%_0.125W_100PPM")
        (field (name "POWER") "0.125W")
        (field (name "AUTHOR") "CERN DEM JLC")
      )
      (libsource (lib "Resistors") (part "Resistor - 1%"))
    )
    (comp (ref "R39")
      (value "40k2")
      (footprint "RESC2012X60N")
      (description "Resistor - 1%")
      (fields
        (field (name "PART NUMBER") "R0805_40K2_1%_0.125W_100PPM")
        (field (name "POWER") "0.125W")
        (field (name "AUTHOR") "CERN DEM JLC")
      )
      (libsource (lib "Resistors") (part "Resistor - 1%"))
    )
    (comp (ref "R40")
      (value "PTV09")
      (footprint "PTV09A-1x30")
      (description "PTV09 Series - 9 mm Potentiometer")
      (libsource (lib "PTV09") (part "PTV09"))
    )
    (comp (ref "R42")
      (value "40k2")
      (footprint "RESC2012X60N")
      (description "Resistor - 1%")
      (fields
        (field (name "PART NUMBER") "R0805_40K2_1%_0.125W_100PPM")
        (field (name "POWER") "0.125W")
        (field (name "AUTHOR") "CERN DEM JLC")
      )
      (libsource (lib "Resistors") (part "Resistor - 1%"))
    )
    (comp (ref "R43")
      (value "40k2")
      (footprint "RESC2012X60N")
      (description "Resistor - 1%")
      (fields
        (field (name "PART NUMBER") "R0805_40K2_1%_0.125W_100PPM")
        (field (name "POWER") "0.125W")
        (field (name "AUTHOR") "CERN DEM JLC")
      )
      (libsource (lib "Resistors") (part "Resistor - 1%"))
    )
    (comp (ref "R44")
      (value "40k2")
      (footprint "RESC2012X60N")
      (description "Resistor - 1%")
      (fields
        (field (name "PART NUMBER") "R0805_40K2_1%_0.125W_100PPM")
        (field (name "POWER") "0.125W")
        (field (name "AUTHOR") "CERN DEM JLC")
      )
      (libsource (lib "Resistors") (part "Resistor - 1%"))
    )
    (comp (ref "T1")
      (value "~")
      (footprint "TO254P1524X483-3N-R750X1016")
      (description "N-CHANNEL MOSFET WITH ZENER DIODE")
      (libsource (lib "Transistors") (part "N-MOSFET-DZ 1G 2D 3S"))
    )
    (comp (ref "T2")
      (value "~")
      (footprint "TO254P1524X483-3N-R750X1016")
      (description "N-CHANNEL MOSFET WITH ZENER DIODE")
      (libsource (lib "Transistors") (part "N-MOSFET-DZ 1G 2D 3S"))
    )
    (comp (ref "T3")
      (value "~")
      (footprint "TO254P1524X483-3N-R750X1016")
      (description "N-CHANNEL MOSFET WITH ZENER DIODE")
      (libsource (lib "Transistors") (part "N-MOSFET-DZ 1G 2D 3S"))
    )
    (comp (ref "T4")
      (value "~")
      (footprint "TO254P1524X483-3N-R750X1016")
      (description "N-CHANNEL MOSFET WITH ZENER DIODE")
      (libsource (lib "Transistors") (part "N-MOSFET-DZ 1G 2D 3S"))
    )
    (comp (ref "T5")
      (value "~")
      (footprint "TO254P1524X483-3N-R750X1016")
      (description "N-CHANNEL MOSFET WITH ZENER DIODE")
      (libsource (lib "Transistors") (part "N-MOSFET-DZ 1G 2D 3S"))
    )
    (comp (ref "T6")
      (value "~")
      (footprint "TO254P1524X483-3N-R750X1016")
      (description "N-CHANNEL MOSFET WITH ZENER DIODE")
      (libsource (lib "Transistors") (part "N-MOSFET-DZ 1G 2D 3S"))
    )
    (comp (ref "TP1")
      (value "Test Point")
      (footprint "VERO_20-313145")
      (fields
        (field (name "PART NUMBER") "VERO_20-313145")
        (field (name "MANUFACTURER") "VERO TECHNOLOGIES")
        (field (name "MANUFACTURER PART NUMBER") "20-313145")
        (field (name "AUTHOR") "CERN DEM JLC")
      )
      (libsource (lib "Connectors") (part "Test Point"))
    )
    (comp (ref "TP2")
      (value "Test Point")
      (footprint "VERO_20-313145")
      (fields
        (field (name "PART NUMBER") "VERO_20-313145")
        (field (name "MANUFACTURER") "VERO TECHNOLOGIES")
        (field (name "MANUFACTURER PART NUMBER") "20-313145")
        (field (name "AUTHOR") "CERN DEM JLC")
      )
      (libsource (lib "Connectors") (part "Test Point"))
    )
    (comp (ref "TP3")
      (value "Test Point")
      (footprint "VERO_20-313145")
      (fields
        (field (name "PART NUMBER") "VERO_20-313145")
        (field (name "MANUFACTURER") "VERO TECHNOLOGIES")
        (field (name "MANUFACTURER PART NUMBER") "20-313145")
        (field (name "AUTHOR") "CERN DEM JLC")
      )
      (libsource (lib "Connectors") (part "Test Point"))
    )
    (comp (ref "TP4")
      (value "Test Point")
      (footprint "VERO_20-313145")
      (fields
        (field (name "PART NUMBER") "VERO_20-313145")
        (field (name "MANUFACTURER") "VERO TECHNOLOGIES")
        (field (name "MANUFACTURER PART NUMBER") "20-313145")
        (field (name "AUTHOR") "CERN DEM JLC")
      )
      (libsource (lib "Connectors") (part "Test Point"))
    )
    (comp (ref "TP5")
      (value "Test Point")
      (footprint "VERO_20-313145")
      (fields
        (field (name "PART NUMBER") "VERO_20-313145")
        (field (name "MANUFACTURER") "VERO TECHNOLOGIES")
        (field (name "MANUFACTURER PART NUMBER") "20-313145")
        (field (name "AUTHOR") "CERN DEM JLC")
      )
      (libsource (lib "Connectors") (part "Test Point"))
    )
    (comp (ref "TP6")
      (value "Test Point")
      (footprint "VERO_20-313145")
      (fields
        (field (name "PART NUMBER") "VERO_20-313145")
        (field (name "MANUFACTURER") "VERO TECHNOLOGIES")
        (field (name "MANUFACTURER PART NUMBER") "20-313145")
        (field (name "AUTHOR") "CERN DEM JLC")
      )
      (libsource (lib "Connectors") (part "Test Point"))
    )
    (comp (ref "U*1")
      (value "L6387ED")
      (footprint "SOIC127P600X175-8N")
      (libsource (lib "lib") (part "L6387ED"))
    )
    (comp (ref "U*2")
      (value "L6387ED")
      (footprint "SOIC127P600X175-8N")
      (libsource (lib "lib") (part "L6387ED"))
    )
    (comp (ref "U*3")
      (value "L6387ED")
      (footprint "SOIC127P600X175-8N")
      (libsource (lib "lib") (part "L6387ED"))
    )
    (comp (ref "U*4")
      (value "L6387ED")
      (footprint "SOIC127P600X175-8N")
      (libsource (lib "lib") (part "L6387ED"))
    )
    (comp (ref "U1")
      (value "LM2596 Step Down Voltage regulator")
      (footprint "LM2596 DC-DC")
      (libsource (lib "AltiumLibraryDDT") (part "LM2596 Step Down Board"))
    )
  )
  (nets
    (net (code "1") (name "+3.3") (class "Default")
      (node (ref "*") (pin "1") (pinfunction "VBAT_1") (pintype "passive"))
      (node (ref "*") (pin "16") (pinfunction "VDD_16") (pintype "passive"))
      (node (ref "*") (pin "28") (pinfunction "VREF+_28") (pintype "passive"))
      (node (ref "*") (pin "29") (pinfunction "VDDA_29") (pintype "passive"))
      (node (ref "*") (pin "32") (pinfunction "VDD_32") (pintype "passive"))
      (node (ref "*") (pin "48") (pinfunction "VDD_48") (pintype "passive"))
      (node (ref "*") (pin "64") (pinfunction "VDD_64") (pintype "passive"))
      (node (ref "C17") (pin "2") (pinfunction "2_2") (pintype "passive"))
      (node (ref "C22") (pin "2") (pinfunction "2_2") (pintype "passive"))
      (node (ref "C23") (pin "2") (pinfunction "2_2") (pintype "passive"))
      (node (ref "C30") (pin "2") (pinfunction "2_2") (pintype "passive"))
      (node (ref "C4") (pin "2") (pinfunction "2_2") (pintype "passive"))
      (node (ref "C42") (pin "2") (pinfunction "2_2") (pintype "passive"))
      (node (ref "C7") (pin "2") (pinfunction "2_2") (pintype "passive"))
      (node (ref "C8") (pin "2") (pinfunction "2_2") (pintype "passive"))
      (node (ref "D5") (pin "1") (pinfunction "C_1") (pintype "passive"))
      (node (ref "J13") (pin "2") (pinfunction "2_2") (pintype "bidirectional"))
      (node (ref "J16") (pin "1") (pinfunction "1_1") (pintype "bidirectional"))
      (node (ref "P1") (pin "1") (pinfunction "1_1") (pintype "passive"))
      (node (ref "R1") (pin "1") (pinfunction "1_1") (pintype "passive"))
      (node (ref "R15") (pin "1") (pinfunction "1_1") (pintype "passive"))
      (node (ref "R2") (pin "2") (pinfunction "2_2") (pintype "passive"))
      (node (ref "R23") (pin "2") (pinfunction "OUT_2") (pintype "passive"))
      (node (ref "R25") (pin "2") (pinfunction "2_2") (pintype "passive"))
      (node (ref "R26") (pin "2") (pinfunction "2_2") (pintype "passive"))
      (node (ref "R27") (pin "2") (pinfunction "2_2") (pintype "passive"))
      (node (ref "R3") (pin "2") (pinfunction "2_2") (pintype "passive"))
      (node (ref "R40") (pin "3") (pinfunction "3_3") (pintype "passive"))
    )
    (net (code "2") (name "+5") (class "Default")
      (node (ref "C29") (pin "2") (pinfunction "2_2") (pintype "passive"))
      (node (ref "C32") (pin "2") (pinfunction "2_2") (pintype "passive"))
      (node (ref "J20") (pin "1") (pinfunction "1_1") (pintype "bidirectional"))
      (node (ref "P1") (pin "3") (pinfunction "3_3") (pintype "passive"))
      (node (ref "R14") (pin "1") (pinfunction "1_1") (pintype "passive"))
      (node (ref "R23") (pin "3") (pinfunction "IN_3") (pintype "passive"))
      (node (ref "R24") (pin "2") (pinfunction "OUT_2") (pintype "passive"))
      (node (ref "U*1") (pin "3") (pinfunction "VCC_3") (pintype "passive"))
    )
    (net (code "3") (name "+5_EXT") (class "Default")
      (node (ref "J15") (pin "1") (pinfunction "1_1") (pintype "bidirectional"))
      (node (ref "J18") (pin "1") (pinfunction "1_1") (pintype "bidirectional"))
      (node (ref "J18") (pin "2") (pinfunction "2_2") (pintype "bidirectional"))
    )
    (net (code "4") (name "+10") (class "Default")
      (node (ref "C12") (pin "2") (pinfunction "2_2") (pintype "passive"))
      (node (ref "C20") (pin "2") (pinfunction "2_2") (pintype "passive"))
      (node (ref "C27") (pin "2") (pinfunction "2_2") (pintype "passive"))
      (node (ref "C31") (pin "2") (pinfunction "2_2") (pintype "passive"))
      (node (ref "D2") (pin "2") (pinfunction "A_2") (pintype "passive"))
      (node (ref "D3") (pin "2") (pinfunction "A_2") (pintype "passive"))
      (node (ref "D4") (pin "2") (pinfunction "A_2") (pintype "passive"))
      (node (ref "R19") (pin "1") (pinfunction "1_1") (pintype "passive"))
      (node (ref "R24") (pin "3") (pinfunction "IN_3") (pintype "passive"))
      (node (ref "U*2") (pin "3") (pinfunction "VCC_3") (pintype "passive"))
      (node (ref "U*3") (pin "3") (pinfunction "VCC_3") (pintype "passive"))
      (node (ref "U*4") (pin "3") (pinfunction "VCC_3") (pintype "passive"))
      (node (ref "U1") (pin "4") (pinfunction "Vout+_4") (pintype "passive"))
    )
    (net (code "5") (name "/BUTTON") (class "Default")
      (node (ref "*") (pin "39") (pinfunction "PC7_39") (pintype "passive"))
      (node (ref "C3") (pin "1") (pinfunction "1_1") (pintype "passive"))
      (node (ref "PB1") (pin "1") (pinfunction "1_1") (pintype "passive"))
      (node (ref "PB1") (pin "2") (pinfunction "2_2") (pintype "passive"))
      (node (ref "R1") (pin "2") (pinfunction "2_2") (pintype "passive"))
    )
    (net (code "6") (name "/CAN_RX") (class "Default")
      (node (ref "*") (pin "61") (pinfunction "PB8-BOOT0_61") (pintype "passive"))
      (node (ref "U*1") (pin "4") (pinfunction "GND_4") (pintype "passive"))
    )
    (net (code "7") (name "/CAN_TX") (class "Default")
      (node (ref "*") (pin "46") (pinfunction "PA12_46") (pintype "passive"))
      (node (ref "U*1") (pin "1") (pinfunction "LIN_1") (pintype "passive"))
    )
    (net (code "8") (name "/Curr_fdbk1_OPAmp+") (class "Default")
      (node (ref "*") (pin "13") (pinfunction "PA1_13") (pintype "passive"))
      (node (ref "R25") (pin "1") (pinfunction "1_1") (pintype "passive"))
      (node (ref "R28") (pin "1") (pinfunction "1_1") (pintype "passive"))
      (node (ref "R37") (pin "2") (pinfunction "2_2") (pintype "passive"))
    )
    (net (code "9") (name "/Curr_fdbk1_OPAmp-") (class "Default")
      (node (ref "*") (pin "17") (pinfunction "PA3_17") (pintype "passive"))
      (node (ref "R33") (pin "2") (pinfunction "2_2") (pintype "passive"))
    )
    (net (code "10") (name "/Curr_fdbk2_OPAmp+") (class "Default")
      (node (ref "*") (pin "21") (pinfunction "PA7_21") (pintype "passive"))
      (node (ref "R26") (pin "1") (pinfunction "1_1") (pintype "passive"))
      (node (ref "R32") (pin "1") (pinfunction "1_1") (pintype "passive"))
      (node (ref "R38") (pin "2") (pinfunction "2_2") (pintype "passive"))
    )
    (net (code "11") (name "/Curr_fdbk2_OPAmp-") (class "Default")
      (node (ref "*") (pin "19") (pinfunction "PA5_19") (pintype "passive"))
      (node (ref "R34") (pin "2") (pinfunction "2_2") (pintype "passive"))
    )
    (net (code "12") (name "/Curr_fdbk3_OPAmp+") (class "Default")
      (node (ref "*") (pin "24") (pinfunction "PB0_24") (pintype "passive"))
      (node (ref "R27") (pin "1") (pinfunction "1_1") (pintype "passive"))
      (node (ref "R36") (pin "1") (pinfunction "1_1") (pintype "passive"))
      (node (ref "R39") (pin "2") (pinfunction "2_2") (pintype "passive"))
    )
    (net (code "13") (name "/Curr_fdbk3_OPAmp-") (class "Default")
      (node (ref "*") (pin "26") (pinfunction "PB2_26") (pintype "passive"))
      (node (ref "R35") (pin "2") (pinfunction "2_2") (pintype "passive"))
    )
    (net (code "14") (name "/I2C_SCL") (class "Default")
      (node (ref "*") (pin "51") (pinfunction "PA15_51") (pintype "passive"))
      (node (ref "J1") (pin "1") (pinfunction "1_1") (pintype "bidirectional"))
      (node (ref "R2") (pin "1") (pinfunction "1_1") (pintype "passive"))
    )
    (net (code "15") (name "/I2C_SDA") (class "Default")
      (node (ref "*") (pin "62") (pinfunction "PB9_62") (pintype "passive"))
      (node (ref "J1") (pin "2") (pinfunction "2_2") (pintype "bidirectional"))
      (node (ref "R3") (pin "1") (pinfunction "1_1") (pintype "passive"))
    )
    (net (code "16") (name "/NRST") (class "Default")
      (node (ref "*") (pin "7") (pinfunction "PG10-NRST_7") (pintype "passive"))
      (node (ref "C14") (pin "2") (pinfunction "2_2") (pintype "passive"))
      (node (ref "J13") (pin "1") (pinfunction "1_1") (pintype "bidirectional"))
    )
    (net (code "17") (name "/OP1_OUT") (class "Default")
      (node (ref "*") (pin "14") (pinfunction "PA2_14") (pintype "passive"))
      (node (ref "TP2") (pin "1") (pinfunction "1_1") (pintype "bidirectional"))
    )
    (net (code "18") (name "/OP2_OUT") (class "Default")
      (node (ref "*") (pin "20") (pinfunction "PA6_20") (pintype "passive"))
      (node (ref "TP1") (pin "1") (pinfunction "1_1") (pintype "bidirectional"))
    )
    (net (code "19") (name "/OP3_OUT") (class "Default")
      (node (ref "*") (pin "25") (pinfunction "PB1_25") (pintype "passive"))
      (node (ref "TP3") (pin "1") (pinfunction "1_1") (pintype "bidirectional"))
    )
    (net (code "20") (name "/OUT1") (class "Default")
      (node (ref "C5") (pin "2") (pinfunction "2_2") (pintype "passive"))
      (node (ref "J12") (pin "3") (pinfunction "3_3") (pintype "bidirectional"))
      (node (ref "R5") (pin "1") (pinfunction "1_1") (pintype "passive"))
      (node (ref "R6") (pin "2") (pinfunction "2_2") (pintype "passive"))
      (node (ref "T1") (pin "3") (pinfunction "S_3") (pintype "passive"))
      (node (ref "T2") (pin "2") (pinfunction "D_2") (pintype "passive"))
      (node (ref "TP4") (pin "1") (pinfunction "1_1") (pintype "bidirectional"))
      (node (ref "U*2") (pin "6") (pinfunction "OUT_P_6") (pintype "passive"))
    )
    (net (code "21") (name "/OUT2") (class "Default")
      (node (ref "C16") (pin "2") (pinfunction "2_2") (pintype "passive"))
      (node (ref "J12") (pin "2") (pinfunction "2_2") (pintype "bidirectional"))
      (node (ref "R10") (pin "1") (pinfunction "1_1") (pintype "passive"))
      (node (ref "R11") (pin "2") (pinfunction "2_2") (pintype "passive"))
      (node (ref "T3") (pin "3") (pinfunction "S_3") (pintype "passive"))
      (node (ref "T4") (pin "2") (pinfunction "D_2") (pintype "passive"))
      (node (ref "TP5") (pin "1") (pinfunction "1_1") (pintype "bidirectional"))
      (node (ref "U*3") (pin "6") (pinfunction "OUT_P_6") (pintype "passive"))
    )
    (net (code "22") (name "/OUT3") (class "Default")
      (node (ref "C24") (pin "2") (pinfunction "2_2") (pintype "passive"))
      (node (ref "J12") (pin "1") (pinfunction "1_1") (pintype "bidirectional"))
      (node (ref "R18") (pin "1") (pinfunction "1_1") (pintype "passive"))
      (node (ref "R20") (pin "2") (pinfunction "2_2") (pintype "passive"))
      (node (ref "T5") (pin "3") (pinfunction "S_3") (pintype "passive"))
      (node (ref "T6") (pin "2") (pinfunction "D_2") (pintype "passive"))
      (node (ref "TP6") (pin "1") (pinfunction "1_1") (pintype "bidirectional"))
      (node (ref "U*4") (pin "6") (pinfunction "OUT_P_6") (pintype "passive"))
    )
    (net (code "23") (name "/POTENTIOMETER") (class "Default")
      (node (ref "*") (pin "33") (pinfunction "PB11_33") (pintype "passive"))
      (node (ref "C15") (pin "2") (pinfunction "2_2") (pintype "passive"))
      (node (ref "R40") (pin "2") (pinfunction "2_2") (pintype "passive"))
    )
    (net (code "24") (name "/SPI2_CSn") (class "Default")
      (node (ref "*") (pin "55") (pinfunction "PD2_55") (pintype "passive"))
      (node (ref "J2") (pin "1") (pinfunction "1_1") (pintype "bidirectional"))
    )
    (net (code "25") (name "/SPI2_MISO") (class "Default")
      (node (ref "*") (pin "57") (pinfunction "PB4_57") (pintype "passive"))
      (node (ref "J2") (pin "3") (pinfunction "3_3") (pintype "bidirectional"))
    )
    (net (code "26") (name "/SPI2_MOSI") (class "Default")
      (node (ref "*") (pin "58") (pinfunction "PB5_58") (pintype "passive"))
      (node (ref "J2") (pin "2") (pinfunction "2_2") (pintype "bidirectional"))
    )
    (net (code "27") (name "/SPI2_SCK") (class "Default")
      (node (ref "*") (pin "56") (pinfunction "PB3_56") (pintype "passive"))
      (node (ref "J2") (pin "4") (pinfunction "4_4") (pintype "bidirectional"))
    )
    (net (code "28") (name "/STATUS") (class "Default")
      (node (ref "*") (pin "38") (pinfunction "PC6_38") (pintype "passive"))
      (node (ref "R16") (pin "1") (pinfunction "1_1") (pintype "passive"))
    )
    (net (code "29") (name "/SWCLK") (class "Default")
      (node (ref "*") (pin "50") (pinfunction "PA14_50") (pintype "passive"))
      (node (ref "J8") (pin "1") (pinfunction "1_1") (pintype "bidirectional"))
    )
    (net (code "30") (name "/SWDIO") (class "Default")
      (node (ref "*") (pin "49") (pinfunction "PA13_49") (pintype "passive"))
      (node (ref "J8") (pin "2") (pinfunction "2_2") (pintype "bidirectional"))
    )
    (net (code "31") (name "/TIM1_CH1") (class "Default")
      (node (ref "*") (pin "42") (pinfunction "PA8_42") (pintype "passive"))
      (node (ref "C11") (pin "2") (pinfunction "2_2") (pintype "passive"))
      (node (ref "J4") (pin "2") (pinfunction "2_2") (pintype "bidirectional"))
      (node (ref "U*2") (pin "2") (pinfunction "HIN_2") (pintype "passive"))
    )
    (net (code "32") (name "/TIM1_CH1N") (class "Default")
      (node (ref "*") (pin "45") (pinfunction "PA11_45") (pintype "passive"))
      (node (ref "C10") (pin "2") (pinfunction "2_2") (pintype "passive"))
      (node (ref "J4") (pin "1") (pinfunction "1_1") (pintype "bidirectional"))
      (node (ref "U*2") (pin "1") (pinfunction "LIN_1") (pintype "passive"))
    )
    (net (code "33") (name "/TIM1_CH2") (class "Default")
      (node (ref "*") (pin "43") (pinfunction "PA9_43") (pintype "passive"))
      (node (ref "C19") (pin "2") (pinfunction "2_2") (pintype "passive"))
      (node (ref "J4") (pin "4") (pinfunction "4_4") (pintype "bidirectional"))
      (node (ref "U*3") (pin "2") (pinfunction "HIN_2") (pintype "passive"))
    )
    (net (code "34") (name "/TIM1_CH2N") (class "Default")
      (node (ref "*") (pin "36") (pinfunction "PB14_36") (pintype "passive"))
      (node (ref "C18") (pin "2") (pinfunction "2_2") (pintype "passive"))
      (node (ref "J4") (pin "3") (pinfunction "3_3") (pintype "bidirectional"))
      (node (ref "U*3") (pin "1") (pinfunction "LIN_1") (pintype "passive"))
    )
    (net (code "35") (name "/TIM1_CH3") (class "Default")
      (node (ref "*") (pin "44") (pinfunction "PA10_44") (pintype "passive"))
      (node (ref "C26") (pin "2") (pinfunction "2_2") (pintype "passive"))
      (node (ref "J4") (pin "6") (pinfunction "6_6") (pintype "bidirectional"))
      (node (ref "U*4") (pin "2") (pinfunction "HIN_2") (pintype "passive"))
    )
    (net (code "36") (name "/TIM1_CH3N") (class "Default")
      (node (ref "*") (pin "37") (pinfunction "PB15_37") (pintype "passive"))
      (node (ref "C25") (pin "2") (pinfunction "2_2") (pintype "passive"))
      (node (ref "J4") (pin "5") (pinfunction "5_5") (pintype "bidirectional"))
      (node (ref "U*4") (pin "1") (pinfunction "LIN_1") (pintype "passive"))
    )
    (net (code "37") (name "/USART2_RX") (class "Default")
      (node (ref "*") (pin "60") (pinfunction "PB7_60") (pintype "passive"))
      (node (ref "J10") (pin "1") (pinfunction "1_1") (pintype "bidirectional"))
    )
    (net (code "38") (name "/USART2_TX") (class "Default")
      (node (ref "*") (pin "59") (pinfunction "PB6_59") (pintype "passive"))
      (node (ref "J10") (pin "2") (pinfunction "2_2") (pintype "bidirectional"))
    )
    (net (code "39") (name "/USB_D+") (class "Default")
      (node (ref "J3") (pin "1") (pinfunction "1_1") (pintype "bidirectional"))
      (node (ref "J7") (pin "1") (pinfunction "1_1") (pintype "bidirectional"))
      (node (ref "J7") (pin "2") (pinfunction "2_2") (pintype "bidirectional"))
    )
    (net (code "40") (name "/USB_D-") (class "Default")
      (node (ref "J3") (pin "2") (pinfunction "2_2") (pintype "bidirectional"))
      (node (ref "J9") (pin "1") (pinfunction "1_1") (pintype "bidirectional"))
      (node (ref "J9") (pin "2") (pinfunction "2_2") (pintype "bidirectional"))
    )
    (net (code "41") (name "/VBUS") (class "Default")
      (node (ref "*") (pin "12") (pinfunction "PA0_12") (pintype "passive"))
      (node (ref "D5") (pin "2") (pinfunction "A_2") (pintype "passive"))
      (node (ref "R42") (pin "1") (pinfunction "1_1") (pintype "passive"))
      (node (ref "R43") (pin "2") (pinfunction "2_2") (pintype "passive"))
    )
    (net (code "42") (name "/Vshunt_1+") (class "Default")
      (node (ref "R28") (pin "2") (pinfunction "2_2") (pintype "passive"))
      (node (ref "R29") (pin "2") (pinfunction "2_2") (pintype "passive"))
      (node (ref "R8") (pin "1") (pinfunction "1_1") (pintype "passive"))
      (node (ref "T2") (pin "3") (pinfunction "S_3") (pintype "passive"))
    )
    (net (code "43") (name "/Vshunt_2+") (class "Default")
      (node (ref "R13") (pin "1") (pinfunction "1_1") (pintype "passive"))
      (node (ref "R30") (pin "2") (pinfunction "2_2") (pintype "passive"))
      (node (ref "R32") (pin "2") (pinfunction "2_2") (pintype "passive"))
      (node (ref "T4") (pin "3") (pinfunction "S_3") (pintype "passive"))
    )
    (net (code "44") (name "/Vshunt_3+") (class "Default")
      (node (ref "R22") (pin "1") (pinfunction "1_1") (pintype "passive"))
      (node (ref "R31") (pin "2") (pinfunction "2_2") (pintype "passive"))
      (node (ref "R36") (pin "2") (pinfunction "2_2") (pintype "passive"))
      (node (ref "T6") (pin "3") (pinfunction "S_3") (pintype "passive"))
    )
    (net (code "45") (name "GND") (class "Default")
      (node (ref "*") (pin "15") (pinfunction "VSS_15") (pintype "passive"))
      (node (ref "*") (pin "27") (pinfunction "VSSA_27") (pintype "passive"))
      (node (ref "*") (pin "31") (pinfunction "VSS_31") (pintype "passive"))
      (node (ref "*") (pin "47") (pinfunction "VSS_47") (pintype "passive"))
      (node (ref "*") (pin "63") (pinfunction "VSS_63") (pintype "passive"))
      (node (ref "*1") (pin "2") (pinfunction "-_2") (pintype "power_in"))
      (node (ref "C1") (pin "2") (pinfunction "2_2") (pintype "passive"))
      (node (ref "C10") (pin "1") (pinfunction "1_1") (pintype "passive"))
      (node (ref "C11") (pin "1") (pinfunction "1_1") (pintype "passive"))
      (node (ref "C12") (pin "1") (pinfunction "1_1") (pintype "passive"))
      (node (ref "C13") (pin "1") (pinfunction "1_1") (pintype "passive"))
      (node (ref "C14") (pin "1") (pinfunction "1_1") (pintype "passive"))
      (node (ref "C15") (pin "1") (pinfunction "1_1") (pintype "passive"))
      (node (ref "C17") (pin "1") (pinfunction "1_1") (pintype "passive"))
      (node (ref "C18") (pin "1") (pinfunction "1_1") (pintype "passive"))
      (node (ref "C19") (pin "1") (pinfunction "1_1") (pintype "passive"))
      (node (ref "C2") (pin "2") (pinfunction "2_2") (pintype "passive"))
      (node (ref "C20") (pin "1") (pinfunction "1_1") (pintype "passive"))
      (node (ref "C21") (pin "1") (pinfunction "1_1") (pintype "passive"))
      (node (ref "C22") (pin "1") (pinfunction "1_1") (pintype "passive"))
      (node (ref "C23") (pin "1") (pinfunction "1_1") (pintype "passive"))
      (node (ref "C25") (pin "1") (pinfunction "1_1") (pintype "passive"))
      (node (ref "C26") (pin "1") (pinfunction "1_1") (pintype "passive"))
      (node (ref "C27") (pin "1") (pinfunction "1_1") (pintype "passive"))
      (node (ref "C28") (pin "1") (pinfunction "1_1") (pintype "passive"))
      (node (ref "C29") (pin "1") (pinfunction "1_1") (pintype "passive"))
      (node (ref "C3") (pin "2") (pinfunction "2_2") (pintype "passive"))
      (node (ref "C30") (pin "1") (pinfunction "1_1") (pintype "passive"))
      (node (ref "C31") (pin "1") (pinfunction "1_1") (pintype "passive"))
      (node (ref "C32") (pin "1") (pinfunction "1_1") (pintype "passive"))
      (node (ref "C33") (pin "1") (pinfunction "1_1") (pintype "passive"))
      (node (ref "C34") (pin "1") (pinfunction "1_1") (pintype "passive"))
      (node (ref "C35") (pin "1") (pinfunction "1_1") (pintype "passive"))
      (node (ref "C36") (pin "1") (pinfunction "1_1") (pintype "passive"))
      (node (ref "C37") (pin "1") (pinfunction "1_1") (pintype "passive"))
      (node (ref "C38") (pin "1") (pinfunction "1_1") (pintype "passive"))
      (node (ref "C39") (pin "1") (pinfunction "1_1") (pintype "passive"))
      (node (ref "C4") (pin "1") (pinfunction "1_1") (pintype "passive"))
      (node (ref "C40") (pin "1") (pinfunction "1_1") (pintype "passive"))
      (node (ref "C41") (pin "1") (pinfunction "1_1") (pintype "passive"))
      (node (ref "C42") (pin "1") (pinfunction "1_1") (pintype "passive"))
      (node (ref "C6") (pin "1") (pinfunction "1_1") (pintype "passive"))
      (node (ref "C7") (pin "1") (pinfunction "1_1") (pintype "passive"))
      (node (ref "C8") (pin "1") (pinfunction "1_1") (pintype "passive"))
      (node (ref "C9") (pin "1") (pinfunction "1_1") (pintype "passive"))
      (node (ref "D1") (pin "2") (pinfunction "A_2") (pintype "passive"))
      (node (ref "J1") (pin "4") (pinfunction "4_4") (pintype "bidirectional"))
      (node (ref "J15") (pin "2") (pinfunction "2_2") (pintype "bidirectional"))
      (node (ref "J16") (pin "2") (pinfunction "2_2") (pintype "bidirectional"))
      (node (ref "J17") (pin "4") (pinfunction "4_4") (pintype "bidirectional"))
      (node (ref "J19") (pin "1") (pinfunction "1_1") (pintype "bidirectional"))
      (node (ref "J19") (pin "2") (pinfunction "2_2") (pintype "bidirectional"))
      (node (ref "J2") (pin "6") (pinfunction "6_6") (pintype "bidirectional"))
      (node (ref "J20") (pin "2") (pinfunction "2_2") (pintype "bidirectional"))
      (node (ref "J6") (pin "1") (pinfunction "1_1") (pintype "bidirectional"))
      (node (ref "J6") (pin "2") (pinfunction "2_2") (pintype "bidirectional"))
      (node (ref "LD1") (pin "1") (pinfunction "C_1") (pintype "passive"))
      (node (ref "LD2") (pin "1") (pinfunction "C_1") (pintype "passive"))
      (node (ref "LD3") (pin "1") (pinfunction "C_1") (pintype "passive"))
      (node (ref "LD4") (pin "1") (pinfunction "C_1") (pintype "passive"))
      (node (ref "LVL_Mx1") (pin "2") (pinfunction "Signal_2") (pintype "passive"))
      (node (ref "PB1") (pin "3") (pinfunction "3_3") (pintype "passive"))
      (node (ref "PB1") (pin "4") (pinfunction "4_4") (pintype "passive"))
      (node (ref "R23") (pin "1") (pinfunction "GND_1") (pintype "passive"))
      (node (ref "R24") (pin "1") (pinfunction "GND_1") (pintype "passive"))
      (node (ref "R29") (pin "1") (pinfunction "1_1") (pintype "passive"))
      (node (ref "R30") (pin "1") (pinfunction "1_1") (pintype "passive"))
      (node (ref "R31") (pin "1") (pinfunction "1_1") (pintype "passive"))
      (node (ref "R33") (pin "1") (pinfunction "1_1") (pintype "passive"))
      (node (ref "R34") (pin "1") (pinfunction "1_1") (pintype "passive"))
      (node (ref "R35") (pin "1") (pinfunction "1_1") (pintype "passive"))
      (node (ref "R37") (pin "1") (pinfunction "1_1") (pintype "passive"))
      (node (ref "R38") (pin "1") (pinfunction "1_1") (pintype "passive"))
      (node (ref "R39") (pin "1") (pinfunction "1_1") (pintype "passive"))
      (node (ref "R40") (pin "1") (pinfunction "1_1") (pintype "passive"))
      (node (ref "R43") (pin "1") (pinfunction "1_1") (pintype "passive"))
      (node (ref "U*1") (pin "2") (pinfunction "HIN_2") (pintype "passive"))
      (node (ref "U*1") (pin "8") (pinfunction "VBOOT_8") (pintype "passive"))
      (node (ref "U*2") (pin "4") (pinfunction "GND_4") (pintype "passive"))
      (node (ref "U*3") (pin "4") (pinfunction "GND_4") (pintype "passive"))
      (node (ref "U*4") (pin "4") (pinfunction "GND_4") (pintype "passive"))
      (node (ref "U1") (pin "1") (pinfunction "Vin-_1") (pintype "passive"))
      (node (ref "U1") (pin "3") (pinfunction "Vout-_3") (pintype "passive"))
    )
    (net (code "46") (name "Net-(*-PF0-OSC_IN)") (class "Default")
      (node (ref "*") (pin "5") (pinfunction "PF0-OSC_IN_5") (pintype "passive"))
      (node (ref "C6") (pin "2") (pinfunction "2_2") (pintype "passive"))
      (node (ref "Q1") (pin "2") (pinfunction "OSC2_2") (pintype "passive"))
    )
    (net (code "47") (name "Net-(*-PF1-OSC_OUT)") (class "Default")
      (node (ref "*") (pin "6") (pinfunction "PF1-OSC_OUT_6") (pintype "passive"))
      (node (ref "C9") (pin "2") (pinfunction "2_2") (pintype "passive"))
      (node (ref "Q1") (pin "1") (pinfunction "OSC1_1") (pintype "passive"))
    )
    (net (code "48") (name "Net-(C13-Pad2)") (class "Default")
      (node (ref "C13") (pin "2") (pinfunction "2_2") (pintype "passive"))
      (node (ref "R6") (pin "1") (pinfunction "1_1") (pintype "passive"))
    )
    (net (code "49") (name "Net-(C21-Pad2)") (class "Default")
      (node (ref "C21") (pin "2") (pinfunction "2_2") (pintype "passive"))
      (node (ref "R11") (pin "1") (pinfunction "1_1") (pintype "passive"))
    )
    (net (code "50") (name "Net-(C28-Pad2)") (class "Default")
      (node (ref "C28") (pin "2") (pinfunction "2_2") (pintype "passive"))
      (node (ref "R20") (pin "1") (pinfunction "1_1") (pintype "passive"))
    )
    (net (code "51") (name "Net-(D2-C)") (class "Default")
      (node (ref "C5") (pin "1") (pinfunction "1_1") (pintype "passive"))
      (node (ref "D2") (pin "1") (pinfunction "C_1") (pintype "passive"))
      (node (ref "U*2") (pin "8") (pinfunction "VBOOT_8") (pintype "passive"))
    )
    (net (code "52") (name "Net-(D3-C)") (class "Default")
      (node (ref "C16") (pin "1") (pinfunction "1_1") (pintype "passive"))
      (node (ref "D3") (pin "1") (pinfunction "C_1") (pintype "passive"))
      (node (ref "U*3") (pin "8") (pinfunction "VBOOT_8") (pintype "passive"))
    )
    (net (code "53") (name "Net-(D4-C)") (class "Default")
      (node (ref "C24") (pin "1") (pinfunction "1_1") (pintype "passive"))
      (node (ref "D4") (pin "1") (pinfunction "C_1") (pintype "passive"))
      (node (ref "U*4") (pin "8") (pinfunction "VBOOT_8") (pintype "passive"))
    )
    (net (code "54") (name "Net-(J1-Pad3)") (class "Default")
      (node (ref "J1") (pin "3") (pinfunction "3_3") (pintype "bidirectional"))
      (node (ref "J2") (pin "5") (pinfunction "5_5") (pintype "bidirectional"))
      (node (ref "P1") (pin "2") (pinfunction "2_2") (pintype "passive"))
    )
    (net (code "55") (name "Net-(LD1-A)") (class "Default")
      (node (ref "LD1") (pin "2") (pinfunction "A_2") (pintype "passive"))
      (node (ref "R14") (pin "2") (pinfunction "2_2") (pintype "passive"))
    )
    (net (code "56") (name "Net-(LD2-A)") (class "Default")
      (node (ref "LD2") (pin "2") (pinfunction "A_2") (pintype "passive"))
      (node (ref "R15") (pin "2") (pinfunction "2_2") (pintype "passive"))
    )
    (net (code "57") (name "Net-(LD3-A)") (class "Default")
      (node (ref "LD3") (pin "2") (pinfunction "A_2") (pintype "passive"))
      (node (ref "R16") (pin "2") (pinfunction "2_2") (pintype "passive"))
    )
    (net (code "58") (name "Net-(LD4-A)") (class "Default")
      (node (ref "LD4") (pin "2") (pinfunction "A_2") (pintype "passive"))
      (node (ref "R19") (pin "2") (pinfunction "2_2") (pintype "passive"))
    )
    (net (code "59") (name "Net-(T1-G)") (class "Default")
      (node (ref "R4") (pin "2") (pinfunction "2_2") (pintype "passive"))
      (node (ref "R5") (pin "2") (pinfunction "2_2") (pintype "passive"))
      (node (ref "T1") (pin "1") (pinfunction "G_1") (pintype "passive"))
    )
    (net (code "60") (name "Net-(T2-G)") (class "Default")
      (node (ref "R7") (pin "2") (pinfunction "2_2") (pintype "passive"))
      (node (ref "R8") (pin "2") (pinfunction "2_2") (pintype "passive"))
      (node (ref "T2") (pin "1") (pinfunction "G_1") (pintype "passive"))
    )
    (net (code "61") (name "Net-(T3-G)") (class "Default")
      (node (ref "R10") (pin "2") (pinfunction "2_2") (pintype "passive"))
      (node (ref "R9") (pin "2") (pinfunction "2_2") (pintype "passive"))
      (node (ref "T3") (pin "1") (pinfunction "G_1") (pintype "passive"))
    )
    (net (code "62") (name "Net-(T4-G)") (class "Default")
      (node (ref "R12") (pin "2") (pinfunction "2_2") (pintype "passive"))
      (node (ref "R13") (pin "2") (pinfunction "2_2") (pintype "passive"))
      (node (ref "T4") (pin "1") (pinfunction "G_1") (pintype "passive"))
    )
    (net (code "63") (name "Net-(T5-G)") (class "Default")
      (node (ref "R17") (pin "2") (pinfunction "2_2") (pintype "passive"))
      (node (ref "R18") (pin "2") (pinfunction "2_2") (pintype "passive"))
      (node (ref "T5") (pin "1") (pinfunction "G_1") (pintype "passive"))
    )
    (net (code "64") (name "Net-(T6-G)") (class "Default")
      (node (ref "R21") (pin "2") (pinfunction "2_2") (pintype "passive"))
      (node (ref "R22") (pin "2") (pinfunction "2_2") (pintype "passive"))
      (node (ref "T6") (pin "1") (pinfunction "G_1") (pintype "passive"))
    )
    (net (code "65") (name "Net-(U*1-HVG(1))") (class "Default")
      (node (ref "J17") (pin "2") (pinfunction "2_2") (pintype "bidirectional"))
      (node (ref "R44") (pin "1") (pinfunction "1_1") (pintype "passive"))
      (node (ref "U*1") (pin "7") (pinfunction "HVG(1)_7") (pintype "passive"))
    )
    (net (code "66") (name "Net-(U*1-OUT_P)") (class "Default")
      (node (ref "J17") (pin "3") (pinfunction "3_3") (pintype "bidirectional"))
      (node (ref "R44") (pin "2") (pinfunction "2_2") (pintype "passive"))
      (node (ref "U*1") (pin "6") (pinfunction "OUT_P_6") (pintype "passive"))
    )
    (net (code "67") (name "Net-(U*2-HVG(1))") (class "Default")
      (node (ref "R4") (pin "1") (pinfunction "1_1") (pintype "passive"))
      (node (ref "U*2") (pin "7") (pinfunction "HVG(1)_7") (pintype "passive"))
    )
    (net (code "68") (name "Net-(U*2-LVG(1))") (class "Default")
      (node (ref "R7") (pin "1") (pinfunction "1_1") (pintype "passive"))
      (node (ref "U*2") (pin "5") (pinfunction "LVG(1)_5") (pintype "passive"))
    )
    (net (code "69") (name "Net-(U*3-HVG(1))") (class "Default")
      (node (ref "R9") (pin "1") (pinfunction "1_1") (pintype "passive"))
      (node (ref "U*3") (pin "7") (pinfunction "HVG(1)_7") (pintype "passive"))
    )
    (net (code "70") (name "Net-(U*3-LVG(1))") (class "Default")
      (node (ref "R12") (pin "1") (pinfunction "1_1") (pintype "passive"))
      (node (ref "U*3") (pin "5") (pinfunction "LVG(1)_5") (pintype "passive"))
    )
    (net (code "71") (name "Net-(U*4-HVG(1))") (class "Default")
      (node (ref "R17") (pin "1") (pinfunction "1_1") (pintype "passive"))
      (node (ref "U*4") (pin "7") (pinfunction "HVG(1)_7") (pintype "passive"))
    )
    (net (code "72") (name "Net-(U*4-LVG(1))") (class "Default")
      (node (ref "R21") (pin "1") (pinfunction "1_1") (pintype "passive"))
      (node (ref "U*4") (pin "5") (pinfunction "LVG(1)_5") (pintype "passive"))
    )
    (net (code "73") (name "V+") (class "Default")
      (node (ref "*1") (pin "1") (pinfunction "+_1") (pintype "power_in"))
      (node (ref "C1") (pin "1") (pinfunction "1_1") (pintype "passive"))
      (node (ref "C2") (pin "1") (pinfunction "1_1") (pintype "passive"))
      (node (ref "C33") (pin "2") (pinfunction "2_2") (pintype "passive"))
      (node (ref "C34") (pin "2") (pinfunction "2_2") (pintype "passive"))
      (node (ref "C35") (pin "2") (pinfunction "2_2") (pintype "passive"))
      (node (ref "C36") (pin "2") (pinfunction "2_2") (pintype "passive"))
      (node (ref "C37") (pin "2") (pinfunction "2_2") (pintype "passive"))
      (node (ref "C38") (pin "2") (pinfunction "2_2") (pintype "passive"))
      (node (ref "C39") (pin "2") (pinfunction "2_2") (pintype "passive"))
      (node (ref "C40") (pin "2") (pinfunction "2_2") (pintype "passive"))
      (node (ref "C41") (pin "2") (pinfunction "2_2") (pintype "passive"))
      (node (ref "D1") (pin "1") (pinfunction "C_1") (pintype "passive"))
      (node (ref "LVL_Mx1") (pin "1") (pinfunction "VCC_1") (pintype "passive"))
      (node (ref "R42") (pin "2") (pinfunction "2_2") (pintype "passive"))
      (node (ref "T1") (pin "2") (pinfunction "D_2") (pintype "passive"))
      (node (ref "T3") (pin "2") (pinfunction "D_2") (pintype "passive"))
      (node (ref "T5") (pin "2") (pinfunction "D_2") (pintype "passive"))
      (node (ref "U1") (pin "2") (pinfunction "Vin+_2") (pintype "passive"))
    )
    (net (code "74") (name "unconnected-(*-PA4-Pad18)") (class "Default")
      (node (ref "*") (pin "18") (pinfunction "PA4_18") (pintype "passive"))
    )
    (net (code "75") (name "unconnected-(*-PB10-Pad30)") (class "Default")
      (node (ref "*") (pin "30") (pinfunction "PB10_30") (pintype "passive"))
    )
    (net (code "76") (name "unconnected-(*-PB12-Pad34)") (class "Default")
      (node (ref "*") (pin "34") (pinfunction "PB12_34") (pintype "passive"))
    )
    (net (code "77") (name "unconnected-(*-PB13-Pad35)") (class "Default")
      (node (ref "*") (pin "35") (pinfunction "PB13_35") (pintype "passive"))
    )
    (net (code "78") (name "unconnected-(*-PC0-Pad8)") (class "Default")
      (node (ref "*") (pin "8") (pinfunction "PC0_8") (pintype "passive"))
    )
    (net (code "79") (name "unconnected-(*-PC1-Pad9)") (class "Default")
      (node (ref "*") (pin "9") (pinfunction "PC1_9") (pintype "passive"))
    )
    (net (code "80") (name "unconnected-(*-PC2-Pad10)") (class "Default")
      (node (ref "*") (pin "10") (pinfunction "PC2_10") (pintype "passive"))
    )
    (net (code "81") (name "unconnected-(*-PC3-Pad11)") (class "Default")
      (node (ref "*") (pin "11") (pinfunction "PC3_11") (pintype "passive"))
    )
    (net (code "82") (name "unconnected-(*-PC4-Pad22)") (class "Default")
      (node (ref "*") (pin "22") (pinfunction "PC4_22") (pintype "passive"))
    )
    (net (code "83") (name "unconnected-(*-PC5-Pad23)") (class "Default")
      (node (ref "*") (pin "23") (pinfunction "PC5_23") (pintype "passive"))
    )
    (net (code "84") (name "unconnected-(*-PC8-Pad40)") (class "Default")
      (node (ref "*") (pin "40") (pinfunction "PC8_40") (pintype "passive"))
    )
    (net (code "85") (name "unconnected-(*-PC9-Pad41)") (class "Default")
      (node (ref "*") (pin "41") (pinfunction "PC9_41") (pintype "passive"))
    )
    (net (code "86") (name "unconnected-(*-PC10-Pad52)") (class "Default")
      (node (ref "*") (pin "52") (pinfunction "PC10_52") (pintype "passive"))
    )
    (net (code "87") (name "unconnected-(*-PC11-Pad53)") (class "Default")
      (node (ref "*") (pin "53") (pinfunction "PC11_53") (pintype "passive"))
    )
    (net (code "88") (name "unconnected-(*-PC12-Pad54)") (class "Default")
      (node (ref "*") (pin "54") (pinfunction "PC12_54") (pintype "passive"))
    )
    (net (code "89") (name "unconnected-(*-PC13-Pad2)") (class "Default")
      (node (ref "*") (pin "2") (pinfunction "PC13_2") (pintype "passive"))
    )
    (net (code "90") (name "unconnected-(*-PC14-OSC32_IN-Pad3)") (class "Default")
      (node (ref "*") (pin "3") (pinfunction "PC14-OSC32_IN_3") (pintype "passive"))
    )
    (net (code "91") (name "unconnected-(*-PC15-OSC32_OUT-Pad4)") (class "Default")
      (node (ref "*") (pin "4") (pinfunction "PC15-OSC32_OUT_4") (pintype "passive"))
    )
    (net (code "92") (name "unconnected-(J5-Pad1)") (class "Default")
      (node (ref "J5") (pin "1") (pinfunction "1_1") (pintype "bidirectional"))
    )
    (net (code "93") (name "unconnected-(J5-Pad2)") (class "Default")
      (node (ref "J5") (pin "2") (pinfunction "2_2") (pintype "bidirectional"))
    )
    (net (code "94") (name "unconnected-(J11-Pad1)") (class "Default")
      (node (ref "J11") (pin "1") (pinfunction "1_1") (pintype "bidirectional"))
    )
    (net (code "95") (name "unconnected-(J11-Pad2)") (class "Default")
      (node (ref "J11") (pin "2") (pinfunction "2_2") (pintype "bidirectional"))
    )
    (net (code "96") (name "unconnected-(J14-Pad1)") (class "Default")
      (node (ref "J14") (pin "1") (pinfunction "1_1") (pintype "bidirectional"))
    )
    (net (code "97") (name "unconnected-(J14-Pad2)") (class "Default")
      (node (ref "J14") (pin "2") (pinfunction "2_2") (pintype "bidirectional"))
    )
    (net (code "98") (name "unconnected-(J17-Pad1)") (class "Default")
      (node (ref "J17") (pin "1") (pinfunction "1_1") (pintype "bidirectional"))
    )
    (net (code "99") (name "unconnected-(R23-Vout-Pad4)") (class "Default")
      (node (ref "R23") (pin "4") (pinfunction "Vout_4") (pintype "output"))
    )
    (net (code "100") (name "unconnected-(R24-Vout-Pad4)") (class "Default")
      (node (ref "R24") (pin "4") (pinfunction "Vout_4") (pintype "output"))
    )
    (net (code "101") (name "unconnected-(U*1-LVG(1)-Pad5)") (class "Default")
      (node (ref "U*1") (pin "5") (pinfunction "LVG(1)_5") (pintype "passive"))
    )
  )
)
